# 201_USB3Hub.net
KiCad netlist of a schematic drawn in Altium Designer
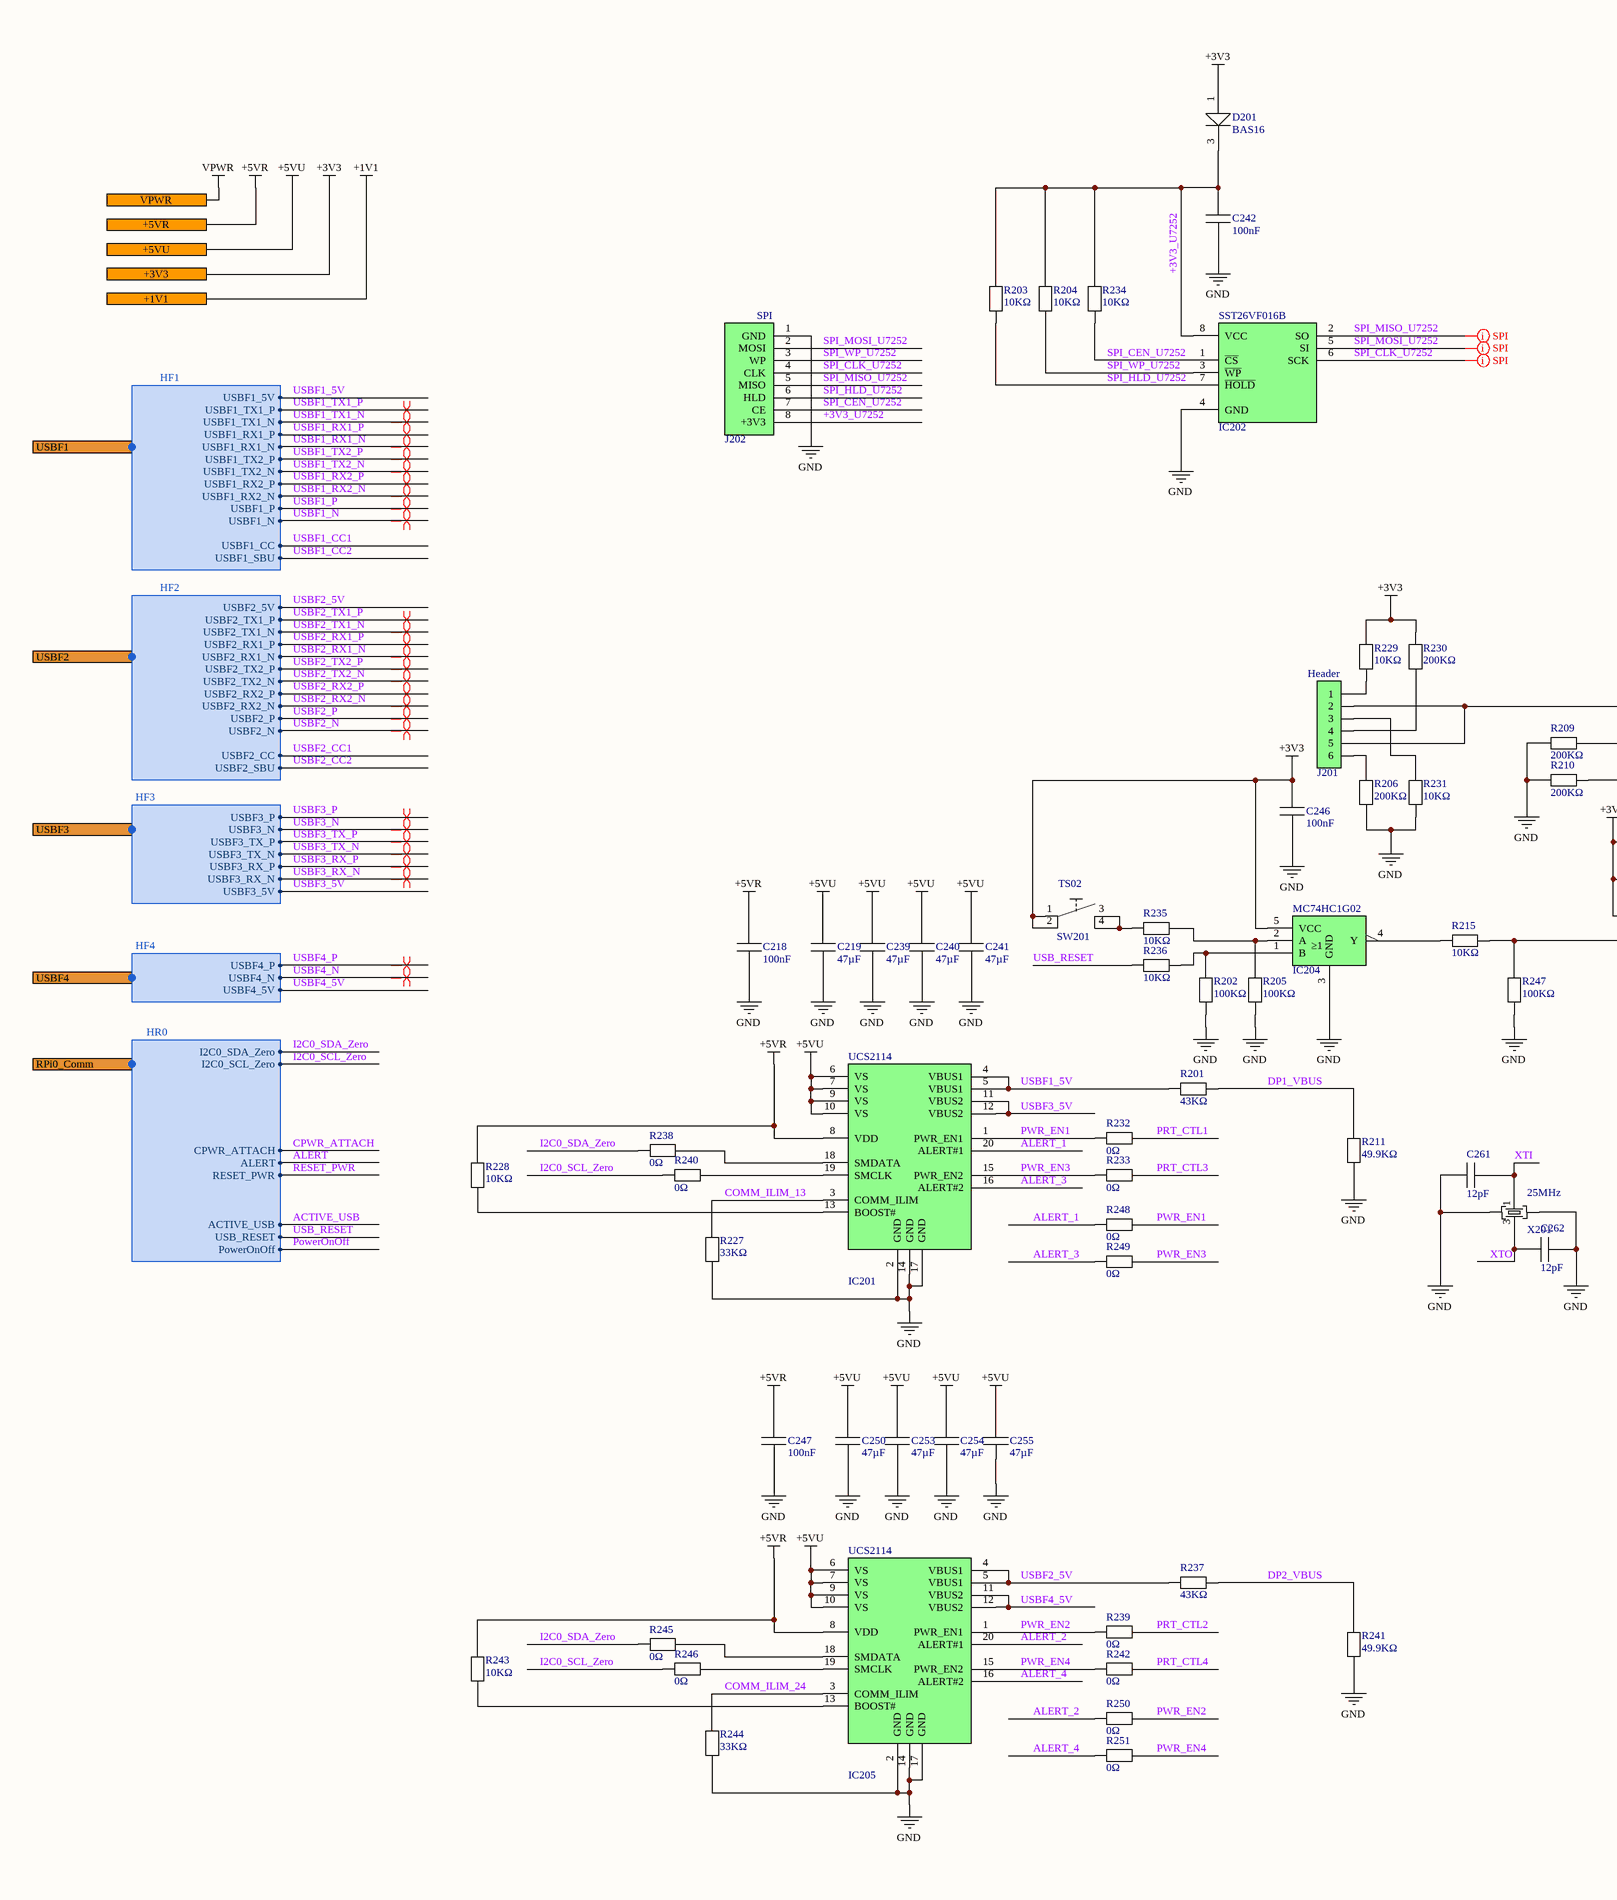
[diagram p0: 201_USB3Hub.SchDoc, left]
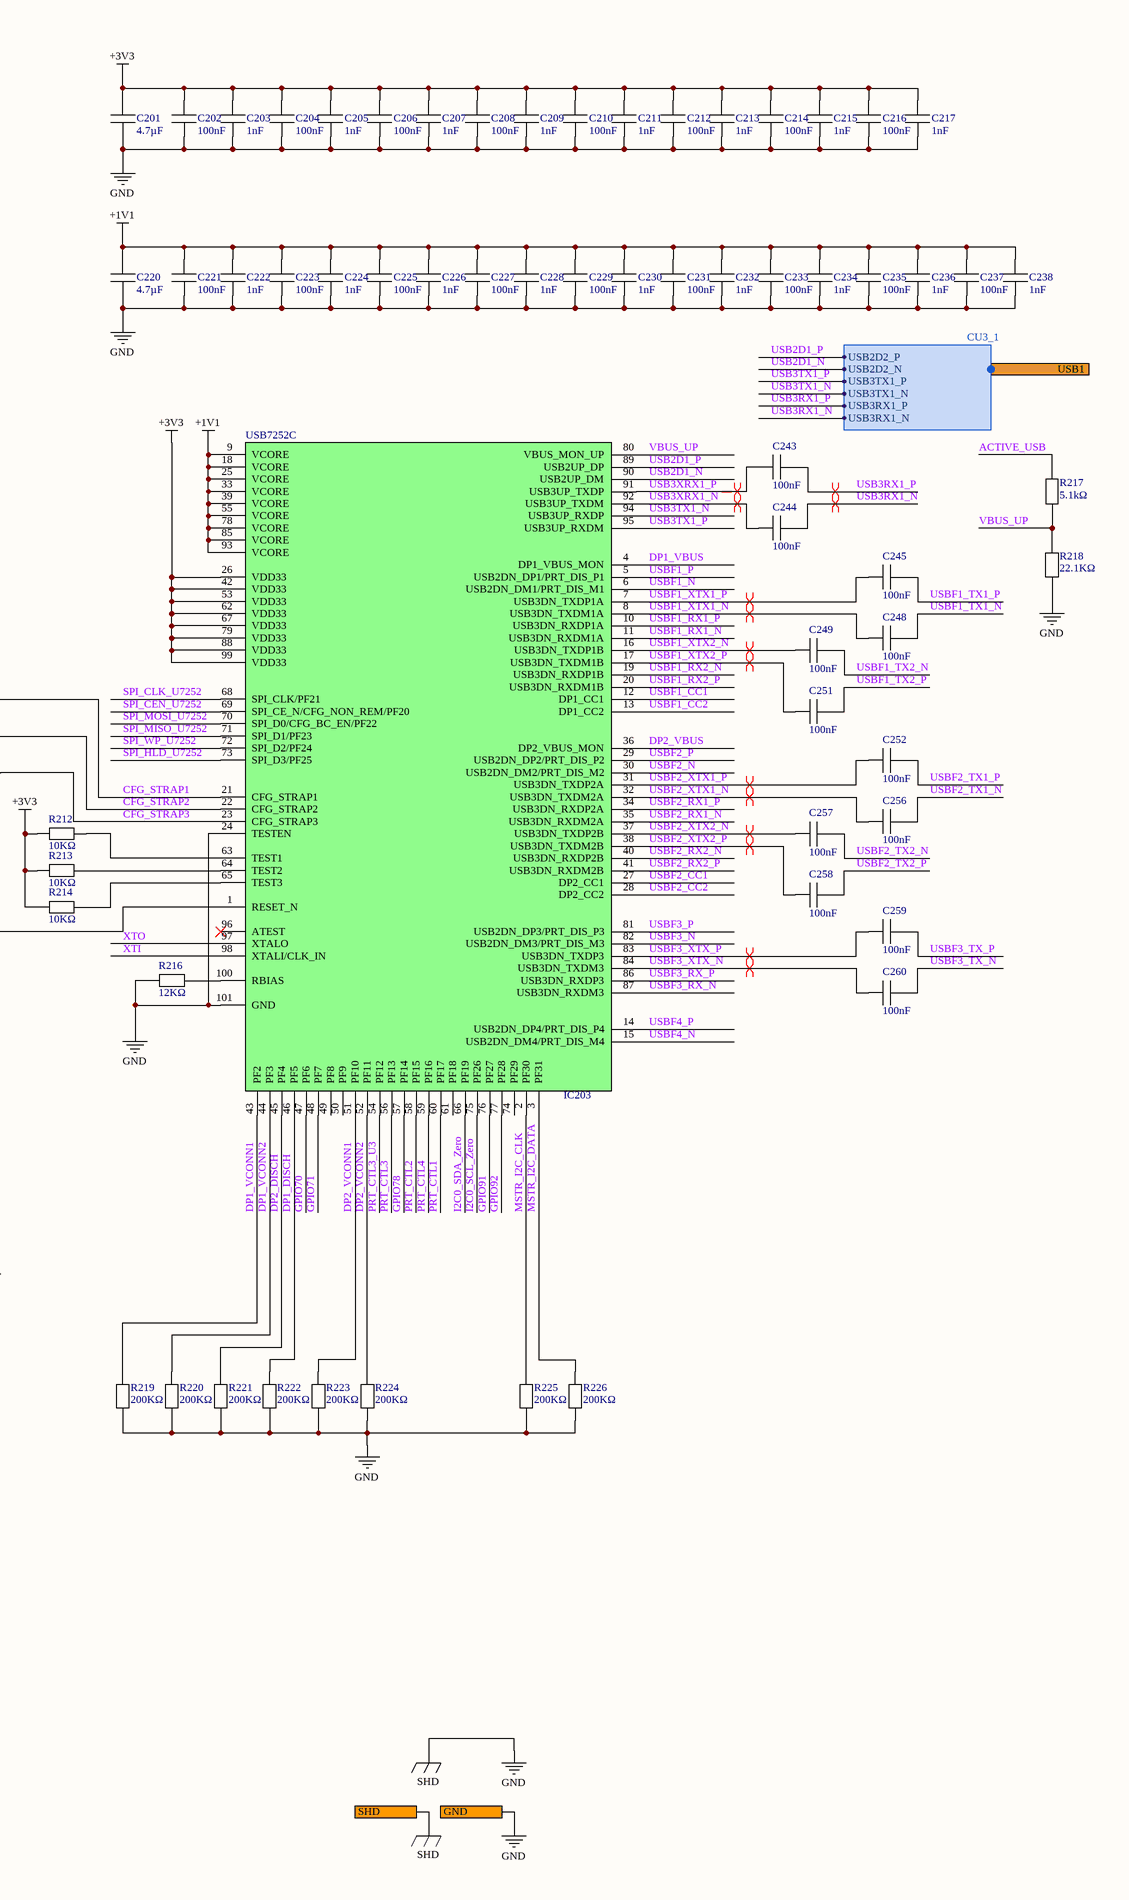
[diagram p1: 201_USB3Hub.SchDoc, right]

(export (version "E")
  (design (tool "Eeschema 10.0.6"))
  (components
    (comp (ref "C201")
      (value "4.7µF")
      (footprint "C0603")
      (description "4.7µF 16V 10% X5R")
      (fields
        (field (name "REFVAL") "4.7µF")
        (field (name "PART NUMBER") "CA0002")
        (field (name "MANFACTPART") "C1608X5R1C475K080AC")
      )
      (libsource (lib "GTS_Database") (part "C"))
    )
    (comp (ref "C202")
      (value "100nF")
      (footprint "C0402")
      (description "100nF 16V 10% X7R")
      (fields
        (field (name "REFVAL") "100nF")
        (field (name "PART NUMBER") "CA0010")
        (field (name "MANFACTPART") "GCM155R71C104KA55D")
      )
      (libsource (lib "GTS_Database") (part "C"))
    )
    (comp (ref "C203")
      (value "1nF")
      (footprint "C0402")
      (description "1nF 50V 1% C0G")
      (fields
        (field (name "REFVAL") "1nF")
        (field (name "PART NUMBER") "CA0031")
        (field (name "MANFACTPART") "GRT1555C1H102FA02D")
      )
      (libsource (lib "GTS_Database") (part "C"))
    )
    (comp (ref "C204")
      (value "100nF")
      (footprint "C0402")
      (description "100nF 16V 10% X7R")
      (fields
        (field (name "REFVAL") "100nF")
        (field (name "PART NUMBER") "CA0010")
        (field (name "MANFACTPART") "GCM155R71C104KA55D")
      )
      (libsource (lib "GTS_Database") (part "C"))
    )
    (comp (ref "C205")
      (value "1nF")
      (footprint "C0402")
      (description "1nF 50V 1% C0G")
      (fields
        (field (name "REFVAL") "1nF")
        (field (name "PART NUMBER") "CA0031")
        (field (name "MANFACTPART") "GRT1555C1H102FA02D")
      )
      (libsource (lib "GTS_Database") (part "C"))
    )
    (comp (ref "C206")
      (value "100nF")
      (footprint "C0402")
      (description "100nF 16V 10% X7R")
      (fields
        (field (name "REFVAL") "100nF")
        (field (name "PART NUMBER") "CA0010")
        (field (name "MANFACTPART") "GCM155R71C104KA55D")
      )
      (libsource (lib "GTS_Database") (part "C"))
    )
    (comp (ref "C207")
      (value "1nF")
      (footprint "C0402")
      (description "1nF 50V 1% C0G")
      (fields
        (field (name "REFVAL") "1nF")
        (field (name "PART NUMBER") "CA0031")
        (field (name "MANFACTPART") "GRT1555C1H102FA02D")
      )
      (libsource (lib "GTS_Database") (part "C"))
    )
    (comp (ref "C208")
      (value "100nF")
      (footprint "C0402")
      (description "100nF 16V 10% X7R")
      (fields
        (field (name "REFVAL") "100nF")
        (field (name "PART NUMBER") "CA0010")
        (field (name "MANFACTPART") "GCM155R71C104KA55D")
      )
      (libsource (lib "GTS_Database") (part "C"))
    )
    (comp (ref "C209")
      (value "1nF")
      (footprint "C0402")
      (description "1nF 50V 1% C0G")
      (fields
        (field (name "REFVAL") "1nF")
        (field (name "PART NUMBER") "CA0031")
        (field (name "MANFACTPART") "GRT1555C1H102FA02D")
      )
      (libsource (lib "GTS_Database") (part "C"))
    )
    (comp (ref "C210")
      (value "100nF")
      (footprint "C0402")
      (description "100nF 16V 10% X7R")
      (fields
        (field (name "REFVAL") "100nF")
        (field (name "PART NUMBER") "CA0010")
        (field (name "MANFACTPART") "GCM155R71C104KA55D")
      )
      (libsource (lib "GTS_Database") (part "C"))
    )
    (comp (ref "C211")
      (value "1nF")
      (footprint "C0402")
      (description "1nF 50V 1% C0G")
      (fields
        (field (name "REFVAL") "1nF")
        (field (name "PART NUMBER") "CA0031")
        (field (name "MANFACTPART") "GRT1555C1H102FA02D")
      )
      (libsource (lib "GTS_Database") (part "C"))
    )
    (comp (ref "C212")
      (value "100nF")
      (footprint "C0402")
      (description "100nF 16V 10% X7R")
      (fields
        (field (name "REFVAL") "100nF")
        (field (name "PART NUMBER") "CA0010")
        (field (name "MANFACTPART") "GCM155R71C104KA55D")
      )
      (libsource (lib "GTS_Database") (part "C"))
    )
    (comp (ref "C213")
      (value "1nF")
      (footprint "C0402")
      (description "1nF 50V 1% C0G")
      (fields
        (field (name "REFVAL") "1nF")
        (field (name "PART NUMBER") "CA0031")
        (field (name "MANFACTPART") "GRT1555C1H102FA02D")
      )
      (libsource (lib "GTS_Database") (part "C"))
    )
    (comp (ref "C214")
      (value "100nF")
      (footprint "C0402")
      (description "100nF 16V 10% X7R")
      (fields
        (field (name "REFVAL") "100nF")
        (field (name "PART NUMBER") "CA0010")
        (field (name "MANFACTPART") "GCM155R71C104KA55D")
      )
      (libsource (lib "GTS_Database") (part "C"))
    )
    (comp (ref "C215")
      (value "1nF")
      (footprint "C0402")
      (description "1nF 50V 1% C0G")
      (fields
        (field (name "REFVAL") "1nF")
        (field (name "PART NUMBER") "CA0031")
        (field (name "MANFACTPART") "GRT1555C1H102FA02D")
      )
      (libsource (lib "GTS_Database") (part "C"))
    )
    (comp (ref "C216")
      (value "100nF")
      (footprint "C0402")
      (description "100nF 16V 10% X7R")
      (fields
        (field (name "REFVAL") "100nF")
        (field (name "PART NUMBER") "CA0010")
        (field (name "MANFACTPART") "GCM155R71C104KA55D")
      )
      (libsource (lib "GTS_Database") (part "C"))
    )
    (comp (ref "C217")
      (value "1nF")
      (footprint "C0402")
      (description "1nF 50V 1% C0G")
      (fields
        (field (name "REFVAL") "1nF")
        (field (name "PART NUMBER") "CA0031")
        (field (name "MANFACTPART") "GRT1555C1H102FA02D")
      )
      (libsource (lib "GTS_Database") (part "C"))
    )
    (comp (ref "C218")
      (value "100nF")
      (footprint "C0402")
      (description "100nF 16V 10% X7R")
      (fields
        (field (name "REFVAL") "100nF")
        (field (name "PART NUMBER") "CA0010")
        (field (name "MANFACTPART") "GCM155R71C104KA55D")
      )
      (libsource (lib "GTS_Database") (part "C"))
    )
    (comp (ref "C219")
      (value "47µF")
      (footprint "C1210")
      (description "47µF 16V 20% X5R")
      (fields
        (field (name "REFVAL") "47µF")
        (field (name "PART NUMBER") "CA0007")
        (field (name "MANFACTPART") "EMK325ABJ476MM8P")
      )
      (libsource (lib "GTS_Database") (part "C"))
    )
    (comp (ref "C220")
      (value "4.7µF")
      (footprint "C0603")
      (description "4.7µF 16V 10% X5R")
      (fields
        (field (name "REFVAL") "4.7µF")
        (field (name "PART NUMBER") "CA0002")
        (field (name "MANFACTPART") "C1608X5R1C475K080AC")
      )
      (libsource (lib "GTS_Database") (part "C"))
    )
    (comp (ref "C221")
      (value "100nF")
      (footprint "C0402")
      (description "100nF 16V 10% X7R")
      (fields
        (field (name "REFVAL") "100nF")
        (field (name "PART NUMBER") "CA0010")
        (field (name "MANFACTPART") "GCM155R71C104KA55D")
      )
      (libsource (lib "GTS_Database") (part "C"))
    )
    (comp (ref "C222")
      (value "1nF")
      (footprint "C0402")
      (description "1nF 50V 1% C0G")
      (fields
        (field (name "REFVAL") "1nF")
        (field (name "PART NUMBER") "CA0031")
        (field (name "MANFACTPART") "GRT1555C1H102FA02D")
      )
      (libsource (lib "GTS_Database") (part "C"))
    )
    (comp (ref "C223")
      (value "100nF")
      (footprint "C0402")
      (description "100nF 16V 10% X7R")
      (fields
        (field (name "REFVAL") "100nF")
        (field (name "PART NUMBER") "CA0010")
        (field (name "MANFACTPART") "GCM155R71C104KA55D")
      )
      (libsource (lib "GTS_Database") (part "C"))
    )
    (comp (ref "C224")
      (value "1nF")
      (footprint "C0402")
      (description "1nF 50V 1% C0G")
      (fields
        (field (name "REFVAL") "1nF")
        (field (name "PART NUMBER") "CA0031")
        (field (name "MANFACTPART") "GRT1555C1H102FA02D")
      )
      (libsource (lib "GTS_Database") (part "C"))
    )
    (comp (ref "C225")
      (value "100nF")
      (footprint "C0402")
      (description "100nF 16V 10% X7R")
      (fields
        (field (name "REFVAL") "100nF")
        (field (name "PART NUMBER") "CA0010")
        (field (name "MANFACTPART") "GCM155R71C104KA55D")
      )
      (libsource (lib "GTS_Database") (part "C"))
    )
    (comp (ref "C226")
      (value "1nF")
      (footprint "C0402")
      (description "1nF 50V 1% C0G")
      (fields
        (field (name "REFVAL") "1nF")
        (field (name "PART NUMBER") "CA0031")
        (field (name "MANFACTPART") "GRT1555C1H102FA02D")
      )
      (libsource (lib "GTS_Database") (part "C"))
    )
    (comp (ref "C227")
      (value "100nF")
      (footprint "C0402")
      (description "100nF 16V 10% X7R")
      (fields
        (field (name "REFVAL") "100nF")
        (field (name "PART NUMBER") "CA0010")
        (field (name "MANFACTPART") "GCM155R71C104KA55D")
      )
      (libsource (lib "GTS_Database") (part "C"))
    )
    (comp (ref "C228")
      (value "1nF")
      (footprint "C0402")
      (description "1nF 50V 1% C0G")
      (fields
        (field (name "REFVAL") "1nF")
        (field (name "PART NUMBER") "CA0031")
        (field (name "MANFACTPART") "GRT1555C1H102FA02D")
      )
      (libsource (lib "GTS_Database") (part "C"))
    )
    (comp (ref "C229")
      (value "100nF")
      (footprint "C0402")
      (description "100nF 16V 10% X7R")
      (fields
        (field (name "REFVAL") "100nF")
        (field (name "PART NUMBER") "CA0010")
        (field (name "MANFACTPART") "GCM155R71C104KA55D")
      )
      (libsource (lib "GTS_Database") (part "C"))
    )
    (comp (ref "C230")
      (value "1nF")
      (footprint "C0402")
      (description "1nF 50V 1% C0G")
      (fields
        (field (name "REFVAL") "1nF")
        (field (name "PART NUMBER") "CA0031")
        (field (name "MANFACTPART") "GRT1555C1H102FA02D")
      )
      (libsource (lib "GTS_Database") (part "C"))
    )
    (comp (ref "C231")
      (value "100nF")
      (footprint "C0402")
      (description "100nF 16V 10% X7R")
      (fields
        (field (name "REFVAL") "100nF")
        (field (name "PART NUMBER") "CA0010")
        (field (name "MANFACTPART") "GCM155R71C104KA55D")
      )
      (libsource (lib "GTS_Database") (part "C"))
    )
    (comp (ref "C232")
      (value "1nF")
      (footprint "C0402")
      (description "1nF 50V 1% C0G")
      (fields
        (field (name "REFVAL") "1nF")
        (field (name "PART NUMBER") "CA0031")
        (field (name "MANFACTPART") "GRT1555C1H102FA02D")
      )
      (libsource (lib "GTS_Database") (part "C"))
    )
    (comp (ref "C233")
      (value "100nF")
      (footprint "C0402")
      (description "100nF 16V 10% X7R")
      (fields
        (field (name "REFVAL") "100nF")
        (field (name "PART NUMBER") "CA0010")
        (field (name "MANFACTPART") "GCM155R71C104KA55D")
      )
      (libsource (lib "GTS_Database") (part "C"))
    )
    (comp (ref "C234")
      (value "1nF")
      (footprint "C0402")
      (description "1nF 50V 1% C0G")
      (fields
        (field (name "REFVAL") "1nF")
        (field (name "PART NUMBER") "CA0031")
        (field (name "MANFACTPART") "GRT1555C1H102FA02D")
      )
      (libsource (lib "GTS_Database") (part "C"))
    )
    (comp (ref "C235")
      (value "100nF")
      (footprint "C0402")
      (description "100nF 16V 10% X7R")
      (fields
        (field (name "REFVAL") "100nF")
        (field (name "PART NUMBER") "CA0010")
        (field (name "MANFACTPART") "GCM155R71C104KA55D")
      )
      (libsource (lib "GTS_Database") (part "C"))
    )
    (comp (ref "C236")
      (value "1nF")
      (footprint "C0402")
      (description "1nF 50V 1% C0G")
      (fields
        (field (name "REFVAL") "1nF")
        (field (name "PART NUMBER") "CA0031")
        (field (name "MANFACTPART") "GRT1555C1H102FA02D")
      )
      (libsource (lib "GTS_Database") (part "C"))
    )
    (comp (ref "C237")
      (value "100nF")
      (footprint "C0402")
      (description "100nF 16V 10% X7R")
      (fields
        (field (name "REFVAL") "100nF")
        (field (name "PART NUMBER") "CA0010")
        (field (name "MANFACTPART") "GCM155R71C104KA55D")
      )
      (libsource (lib "GTS_Database") (part "C"))
    )
    (comp (ref "C238")
      (value "1nF")
      (footprint "C0402")
      (description "1nF 50V 1% C0G")
      (fields
        (field (name "REFVAL") "1nF")
        (field (name "PART NUMBER") "CA0031")
        (field (name "MANFACTPART") "GRT1555C1H102FA02D")
      )
      (libsource (lib "GTS_Database") (part "C"))
    )
    (comp (ref "C239")
      (value "47µF")
      (footprint "C1210")
      (description "47µF 16V 20% X5R")
      (fields
        (field (name "REFVAL") "47µF")
        (field (name "PART NUMBER") "CA0007")
        (field (name "MANFACTPART") "EMK325ABJ476MM8P")
      )
      (libsource (lib "GTS_Database") (part "C"))
    )
    (comp (ref "C240")
      (value "47µF")
      (footprint "C1210")
      (description "47µF 16V 20% X5R")
      (fields
        (field (name "REFVAL") "47µF")
        (field (name "PART NUMBER") "CA0007")
        (field (name "MANFACTPART") "EMK325ABJ476MM8P")
      )
      (libsource (lib "GTS_Database") (part "C"))
    )
    (comp (ref "C241")
      (value "47µF")
      (footprint "C1210")
      (description "47µF 16V 20% X5R")
      (fields
        (field (name "REFVAL") "47µF")
        (field (name "PART NUMBER") "CA0007")
        (field (name "MANFACTPART") "EMK325ABJ476MM8P")
      )
      (libsource (lib "GTS_Database") (part "C"))
    )
    (comp (ref "C242")
      (value "100nF")
      (footprint "C0402")
      (description "100nF 16V 10% X7R")
      (fields
        (field (name "REFVAL") "100nF")
        (field (name "PART NUMBER") "CA0010")
        (field (name "MANFACTPART") "GCM155R71C104KA55D")
      )
      (libsource (lib "GTS_Database") (part "C"))
    )
    (comp (ref "C243")
      (value "100nF")
      (footprint "C0402")
      (description "100nF 16V 10% X7R")
      (fields
        (field (name "REFVAL") "100nF")
        (field (name "PART NUMBER") "CA0010")
        (field (name "MANFACTPART") "GCM155R71C104KA55D")
      )
      (libsource (lib "GTS_Database") (part "C"))
    )
    (comp (ref "C244")
      (value "100nF")
      (footprint "C0402")
      (description "100nF 16V 10% X7R")
      (fields
        (field (name "REFVAL") "100nF")
        (field (name "PART NUMBER") "CA0010")
        (field (name "MANFACTPART") "GCM155R71C104KA55D")
      )
      (libsource (lib "GTS_Database") (part "C"))
    )
    (comp (ref "C245")
      (value "100nF")
      (footprint "C0402")
      (description "100nF 16V 10% X7R")
      (fields
        (field (name "REFVAL") "100nF")
        (field (name "PART NUMBER") "CA0010")
        (field (name "MANFACTPART") "GCM155R71C104KA55D")
      )
      (libsource (lib "GTS_Database") (part "C"))
    )
    (comp (ref "C246")
      (value "100nF")
      (footprint "C0402")
      (description "100nF 16V 10% X7R")
      (fields
        (field (name "REFVAL") "100nF")
        (field (name "PART NUMBER") "CA0010")
        (field (name "MANFACTPART") "GCM155R71C104KA55D")
      )
      (libsource (lib "GTS_Database") (part "C"))
    )
    (comp (ref "C247")
      (value "100nF")
      (footprint "C0402")
      (description "100nF 16V 10% X7R")
      (fields
        (field (name "REFVAL") "100nF")
        (field (name "PART NUMBER") "CA0010")
        (field (name "MANFACTPART") "GCM155R71C104KA55D")
      )
      (libsource (lib "GTS_Database") (part "C"))
    )
    (comp (ref "C248")
      (value "100nF")
      (footprint "C0402")
      (description "100nF 16V 10% X7R")
      (fields
        (field (name "REFVAL") "100nF")
        (field (name "PART NUMBER") "CA0010")
        (field (name "MANFACTPART") "GCM155R71C104KA55D")
      )
      (libsource (lib "GTS_Database") (part "C"))
    )
    (comp (ref "C249")
      (value "100nF")
      (footprint "C0402")
      (description "100nF 16V 10% X7R")
      (fields
        (field (name "REFVAL") "100nF")
        (field (name "PART NUMBER") "CA0010")
        (field (name "MANFACTPART") "GCM155R71C104KA55D")
      )
      (libsource (lib "GTS_Database") (part "C"))
    )
    (comp (ref "C250")
      (value "47µF")
      (footprint "C1210")
      (description "47µF 16V 20% X5R")
      (fields
        (field (name "REFVAL") "47µF")
        (field (name "PART NUMBER") "CA0007")
        (field (name "MANFACTPART") "EMK325ABJ476MM8P")
      )
      (libsource (lib "GTS_Database") (part "C"))
    )
    (comp (ref "C251")
      (value "100nF")
      (footprint "C0402")
      (description "100nF 16V 10% X7R")
      (fields
        (field (name "REFVAL") "100nF")
        (field (name "PART NUMBER") "CA0010")
        (field (name "MANFACTPART") "GCM155R71C104KA55D")
      )
      (libsource (lib "GTS_Database") (part "C"))
    )
    (comp (ref "C252")
      (value "100nF")
      (footprint "C0402")
      (description "100nF 16V 10% X7R")
      (fields
        (field (name "REFVAL") "100nF")
        (field (name "PART NUMBER") "CA0010")
        (field (name "MANFACTPART") "GCM155R71C104KA55D")
      )
      (libsource (lib "GTS_Database") (part "C"))
    )
    (comp (ref "C253")
      (value "47µF")
      (footprint "C1210")
      (description "47µF 16V 20% X5R")
      (fields
        (field (name "REFVAL") "47µF")
        (field (name "PART NUMBER") "CA0007")
        (field (name "MANFACTPART") "EMK325ABJ476MM8P")
      )
      (libsource (lib "GTS_Database") (part "C"))
    )
    (comp (ref "C254")
      (value "47µF")
      (footprint "C1210")
      (description "47µF 16V 20% X5R")
      (fields
        (field (name "REFVAL") "47µF")
        (field (name "PART NUMBER") "CA0007")
        (field (name "MANFACTPART") "EMK325ABJ476MM8P")
      )
      (libsource (lib "GTS_Database") (part "C"))
    )
    (comp (ref "C255")
      (value "47µF")
      (footprint "C1210")
      (description "47µF 16V 20% X5R")
      (fields
        (field (name "REFVAL") "47µF")
        (field (name "PART NUMBER") "CA0007")
        (field (name "MANFACTPART") "EMK325ABJ476MM8P")
      )
      (libsource (lib "GTS_Database") (part "C"))
    )
    (comp (ref "C256")
      (value "100nF")
      (footprint "C0402")
      (description "100nF 16V 10% X7R")
      (fields
        (field (name "REFVAL") "100nF")
        (field (name "PART NUMBER") "CA0010")
        (field (name "MANFACTPART") "GCM155R71C104KA55D")
      )
      (libsource (lib "GTS_Database") (part "C"))
    )
    (comp (ref "C257")
      (value "100nF")
      (footprint "C0402")
      (description "100nF 16V 10% X7R")
      (fields
        (field (name "REFVAL") "100nF")
        (field (name "PART NUMBER") "CA0010")
        (field (name "MANFACTPART") "GCM155R71C104KA55D")
      )
      (libsource (lib "GTS_Database") (part "C"))
    )
    (comp (ref "C258")
      (value "100nF")
      (footprint "C0402")
      (description "100nF 16V 10% X7R")
      (fields
        (field (name "REFVAL") "100nF")
        (field (name "PART NUMBER") "CA0010")
        (field (name "MANFACTPART") "GCM155R71C104KA55D")
      )
      (libsource (lib "GTS_Database") (part "C"))
    )
    (comp (ref "C259")
      (value "100nF")
      (footprint "C0402")
      (description "100nF 16V 10% X7R")
      (fields
        (field (name "REFVAL") "100nF")
        (field (name "PART NUMBER") "CA0010")
        (field (name "MANFACTPART") "GCM155R71C104KA55D")
      )
      (libsource (lib "GTS_Database") (part "C"))
    )
    (comp (ref "C260")
      (value "100nF")
      (footprint "C0402")
      (description "100nF 16V 10% X7R")
      (fields
        (field (name "REFVAL") "100nF")
        (field (name "PART NUMBER") "CA0010")
        (field (name "MANFACTPART") "GCM155R71C104KA55D")
      )
      (libsource (lib "GTS_Database") (part "C"))
    )
    (comp (ref "C261")
      (value "12pF")
      (footprint "C0402")
      (description "12pF 16V 1% C0G")
      (fields
        (field (name "REFVAL") "12pF")
        (field (name "PART NUMBER") "CA0059")
        (field (name "MANFACTPART") "VJ0402A120FXJCW1BC")
      )
      (libsource (lib "GTS_Database") (part "C"))
    )
    (comp (ref "C262")
      (value "12pF")
      (footprint "C0402")
      (description "12pF 16V 1% C0G")
      (fields
        (field (name "REFVAL") "12pF")
        (field (name "PART NUMBER") "CA0059")
        (field (name "MANFACTPART") "VJ0402A120FXJCW1BC")
      )
      (libsource (lib "GTS_Database") (part "C"))
    )
    (comp (ref "D201")
      (value "BAS16")
      (footprint "SOT-23")
      (description "Diodes - General Purpose, Power, Switching 100Vll Signal Switching Diodes 2A")
      (fields
        (field (name "REFVAL") "BAS16")
        (field (name "PART NUMBER") "DI0010")
        (field (name "MANFACTPART") "BAS16_R1_00001")
      )
      (libsource (lib "GTS_Database") (part "Ddefault_3P"))
    )
    (comp (ref "IC201")
      (value "UCS2114")
      (footprint "VQFN-20_3X3")
      (description "Dual USB Power Switch with Integrated Current Sensor")
      (fields (field (name "REFVAL") "UCS2114") (field (name "PART NUMBER") "IC0056"))
      (libsource (lib "GTS_Database") (part "UCS2114"))
    )
    (comp (ref "IC202")
      (value "SST26VF016B")
      (footprint "SO-8")
      (description "16 Mbit Serial Quad I/O (SQI) Flash Memory")
      (fields
        (field (name "REFVAL") "SST26VF016B")
        (field (name "PART NUMBER") "IC0059")
        (field (name "MANFACTPART") "SST26VF016B-104V/SN")
      )
      (libsource (lib "GTS_Database") (part "SST26VF016B"))
    )
    (comp (ref "IC203")
      (value "USB7252C")
      (footprint "VQFN-100G_12X12")
      (description "4-Port USB 3.2 Gen 2 Type-C Controller Hub")
      (fields (field (name "REFVAL") "USB7252C") (field (name "PART NUMBER") "IC0047"))
      (libsource (lib "GTS_Database") (part "USB7252C"))
    )
    (comp (ref "IC204")
      (value "MC74HC1G02")
      (footprint "TSOP-5")
      (description "Logic Gates 2-6V Single 2-Input NOR")
      (fields
        (field (name "REFVAL") "MC74HC1G02")
        (field (name "PART NUMBER") "IC0061")
        (field (name "MANFACTPART") "MC74HC1G02DTT1G")
      )
      (libsource (lib "GTS_Database") (part "MC74HC1G02"))
    )
    (comp (ref "IC205")
      (value "UCS2114")
      (footprint "VQFN-20_3X3")
      (description "Dual USB Power Switch with Integrated Current Sensor")
      (fields (field (name "REFVAL") "UCS2114") (field (name "PART NUMBER") "IC0056"))
      (libsource (lib "GTS_Database") (part "UCS2114"))
    )
    (comp (ref "J201")
      (value "Header")
      (footprint "1X6P_2.54MM_SMT")
      (description "Header 1x6P SMT Mount")
      (fields
        (field (name "REFVAL") "Header")
        (field (name "PART NUMBER") "CO0043")
        (field (name "MANFACTPART") "G800MJ302018EU")
      )
      (libsource (lib "GTS_Database") (part "CONN1X6P"))
    )
    (comp (ref "J202")
      (value "SPI")
      (footprint "SPI_PROG_TYPE1")
      (description "SPI Programming connection")
      (fields (field (name "REFVAL") "SPI") (field (name "PART NUMBER") "ME0028"))
      (libsource (lib "GTS_Database") (part "SPI_PROG_TYPE1"))
    )
    (comp (ref "R201")
      (value "43KΩ")
      (footprint "R0402")
      (description "43KΩ 1% 62.5mW 100PPM")
      (fields
        (field (name "REFVAL") "43KΩ")
        (field (name "PART NUMBER") "RS0076")
        (field (name "MANFACTPART") "CRCW040243K0FKEDC")
      )
      (libsource (lib "GTS_Database") (part "R"))
    )
    (comp (ref "R202")
      (value "100KΩ")
      (footprint "R0402")
      (description "100KΩ 1% 62.5mW 100PPM")
      (fields
        (field (name "REFVAL") "100KΩ")
        (field (name "PART NUMBER") "RS0036")
        (field (name "MANFACTPART") "AC0402FR-13100KL")
      )
      (libsource (lib "GTS_Database") (part "R"))
    )
    (comp (ref "R203")
      (value "10KΩ")
      (footprint "R0402")
      (description "10KΩ 1% 62.5mW")
      (fields
        (field (name "REFVAL") "10KΩ")
        (field (name "PART NUMBER") "RS0011")
        (field (name "MANFACTPART") "WR04X1002FTL")
      )
      (libsource (lib "GTS_Database") (part "R"))
    )
    (comp (ref "R204")
      (value "10KΩ")
      (footprint "R0402")
      (description "10KΩ 1% 62.5mW")
      (fields
        (field (name "REFVAL") "10KΩ")
        (field (name "PART NUMBER") "RS0011")
        (field (name "MANFACTPART") "WR04X1002FTL")
      )
      (libsource (lib "GTS_Database") (part "R"))
    )
    (comp (ref "R205")
      (value "100KΩ")
      (footprint "R0402")
      (description "100KΩ 1% 62.5mW 100PPM")
      (fields
        (field (name "REFVAL") "100KΩ")
        (field (name "PART NUMBER") "RS0036")
        (field (name "MANFACTPART") "AC0402FR-13100KL")
      )
      (libsource (lib "GTS_Database") (part "R"))
    )
    (comp (ref "R206")
      (value "200KΩ")
      (footprint "R0402")
      (description "200KΩ 1% 62.5mW 100PPM")
      (fields
        (field (name "REFVAL") "200KΩ")
        (field (name "PART NUMBER") "RS0045")
        (field (name "MANFACTPART") "CRG0402F200K")
      )
      (libsource (lib "GTS_Database") (part "R"))
    )
    (comp (ref "R209")
      (value "200KΩ")
      (footprint "R0402")
      (description "200KΩ 1% 62.5mW 100PPM")
      (fields
        (field (name "REFVAL") "200KΩ")
        (field (name "PART NUMBER") "RS0045")
        (field (name "MANFACTPART") "CRG0402F200K")
      )
      (libsource (lib "GTS_Database") (part "R"))
    )
    (comp (ref "R210")
      (value "200KΩ")
      (footprint "R0402")
      (description "200KΩ 1% 62.5mW 100PPM")
      (fields
        (field (name "REFVAL") "200KΩ")
        (field (name "PART NUMBER") "RS0045")
        (field (name "MANFACTPART") "CRG0402F200K")
      )
      (libsource (lib "GTS_Database") (part "R"))
    )
    (comp (ref "R211")
      (value "49.9KΩ")
      (footprint "R0402")
      (description "49.9KΩ 1% 62.5mW 100PPM")
      (fields
        (field (name "REFVAL") "49.9KΩ")
        (field (name "PART NUMBER") "RS0077")
        (field (name "MANFACTPART") "0402WGF4992TCE")
      )
      (libsource (lib "GTS_Database") (part "R"))
    )
    (comp (ref "R212")
      (value "10KΩ")
      (footprint "R0402")
      (description "10KΩ 1% 62.5mW")
      (fields
        (field (name "REFVAL") "10KΩ")
        (field (name "PART NUMBER") "RS0011")
        (field (name "MANFACTPART") "WR04X1002FTL")
      )
      (libsource (lib "GTS_Database") (part "R"))
    )
    (comp (ref "R213")
      (value "10KΩ")
      (footprint "R0402")
      (description "10KΩ 1% 62.5mW")
      (fields
        (field (name "REFVAL") "10KΩ")
        (field (name "PART NUMBER") "RS0011")
        (field (name "MANFACTPART") "WR04X1002FTL")
      )
      (libsource (lib "GTS_Database") (part "R"))
    )
    (comp (ref "R214")
      (value "10KΩ")
      (footprint "R0402")
      (description "10KΩ 1% 62.5mW")
      (fields
        (field (name "REFVAL") "10KΩ")
        (field (name "PART NUMBER") "RS0011")
        (field (name "MANFACTPART") "WR04X1002FTL")
      )
      (libsource (lib "GTS_Database") (part "R"))
    )
    (comp (ref "R215")
      (value "10KΩ")
      (footprint "R0402")
      (description "10KΩ 1% 62.5mW")
      (fields
        (field (name "REFVAL") "10KΩ")
        (field (name "PART NUMBER") "RS0011")
        (field (name "MANFACTPART") "WR04X1002FTL")
      )
      (libsource (lib "GTS_Database") (part "R"))
    )
    (comp (ref "R216")
      (value "12KΩ")
      (footprint "R0402")
      (description "12KΩ 1% 62.5mW")
      (fields
        (field (name "REFVAL") "12KΩ")
        (field (name "PART NUMBER") "RS0015")
        (field (name "MANFACTPART") "RC0402FR-1312KL")
      )
      (libsource (lib "GTS_Database") (part "R"))
    )
    (comp (ref "R217")
      (value "5.1kΩ")
      (footprint "R0402")
      (description "5.1KΩ 1% 62.5mW 100PPM")
      (fields
        (field (name "REFVAL") "5.1kΩ")
        (field (name "PART NUMBER") "RS0038")
        (field (name "MANFACTPART") "CRCW04025K10FKEDC")
      )
      (libsource (lib "GTS_Database") (part "R"))
    )
    (comp (ref "R218")
      (value "22.1KΩ")
      (footprint "R0603")
      (description "22.1KΩ 1% 100mW 100PPM")
      (fields
        (field (name "REFVAL") "22.1KΩ")
        (field (name "PART NUMBER") "RS0040")
        (field (name "MANFACTPART") "RC0603FR-0722K1L")
      )
      (libsource (lib "GTS_Database") (part "R"))
    )
    (comp (ref "R219")
      (value "200KΩ")
      (footprint "R0402")
      (description "200KΩ 1% 62.5mW 100PPM")
      (fields
        (field (name "REFVAL") "200KΩ")
        (field (name "PART NUMBER") "RS0045")
        (field (name "MANFACTPART") "CRG0402F200K")
      )
      (libsource (lib "GTS_Database") (part "R"))
    )
    (comp (ref "R220")
      (value "200KΩ")
      (footprint "R0402")
      (description "200KΩ 1% 62.5mW 100PPM")
      (fields
        (field (name "REFVAL") "200KΩ")
        (field (name "PART NUMBER") "RS0045")
        (field (name "MANFACTPART") "CRG0402F200K")
      )
      (libsource (lib "GTS_Database") (part "R"))
    )
    (comp (ref "R221")
      (value "200KΩ")
      (footprint "R0402")
      (description "200KΩ 1% 62.5mW 100PPM")
      (fields
        (field (name "REFVAL") "200KΩ")
        (field (name "PART NUMBER") "RS0045")
        (field (name "MANFACTPART") "CRG0402F200K")
      )
      (libsource (lib "GTS_Database") (part "R"))
    )
    (comp (ref "R222")
      (value "200KΩ")
      (footprint "R0402")
      (description "200KΩ 1% 62.5mW 100PPM")
      (fields
        (field (name "REFVAL") "200KΩ")
        (field (name "PART NUMBER") "RS0045")
        (field (name "MANFACTPART") "CRG0402F200K")
      )
      (libsource (lib "GTS_Database") (part "R"))
    )
    (comp (ref "R223")
      (value "200KΩ")
      (footprint "R0402")
      (description "200KΩ 1% 62.5mW 100PPM")
      (fields
        (field (name "REFVAL") "200KΩ")
        (field (name "PART NUMBER") "RS0045")
        (field (name "MANFACTPART") "CRG0402F200K")
      )
      (libsource (lib "GTS_Database") (part "R"))
    )
    (comp (ref "R224")
      (value "200KΩ")
      (footprint "R0402")
      (description "200KΩ 1% 62.5mW 100PPM")
      (fields
        (field (name "REFVAL") "200KΩ")
        (field (name "PART NUMBER") "RS0045")
        (field (name "MANFACTPART") "CRG0402F200K")
      )
      (libsource (lib "GTS_Database") (part "R"))
    )
    (comp (ref "R225")
      (value "200KΩ")
      (footprint "R0402")
      (description "200KΩ 1% 62.5mW 100PPM")
      (fields
        (field (name "REFVAL") "200KΩ")
        (field (name "PART NUMBER") "RS0045")
        (field (name "MANFACTPART") "CRG0402F200K")
      )
      (libsource (lib "GTS_Database") (part "R"))
    )
    (comp (ref "R226")
      (value "200KΩ")
      (footprint "R0402")
      (description "200KΩ 1% 62.5mW 100PPM")
      (fields
        (field (name "REFVAL") "200KΩ")
        (field (name "PART NUMBER") "RS0045")
        (field (name "MANFACTPART") "CRG0402F200K")
      )
      (libsource (lib "GTS_Database") (part "R"))
    )
    (comp (ref "R227")
      (value "33KΩ")
      (footprint "R0402")
      (description "33KΩ 1% 62.5mW 100PPM")
      (fields
        (field (name "REFVAL") "33KΩ")
        (field (name "PART NUMBER") "RS0075")
        (field (name "MANFACTPART") "0402WGF3302TCE")
      )
      (libsource (lib "GTS_Database") (part "R"))
    )
    (comp (ref "R228")
      (value "10KΩ")
      (footprint "R0402")
      (description "10KΩ 1% 62.5mW")
      (fields
        (field (name "REFVAL") "10KΩ")
        (field (name "PART NUMBER") "RS0011")
        (field (name "MANFACTPART") "WR04X1002FTL")
      )
      (libsource (lib "GTS_Database") (part "R"))
    )
    (comp (ref "R229")
      (value "10KΩ")
      (footprint "R0402")
      (description "10KΩ 1% 62.5mW")
      (fields
        (field (name "REFVAL") "10KΩ")
        (field (name "PART NUMBER") "RS0011")
        (field (name "MANFACTPART") "WR04X1002FTL")
      )
      (libsource (lib "GTS_Database") (part "R"))
    )
    (comp (ref "R230")
      (value "200KΩ")
      (footprint "R0402")
      (description "200KΩ 1% 62.5mW 100PPM")
      (fields
        (field (name "REFVAL") "200KΩ")
        (field (name "PART NUMBER") "RS0045")
        (field (name "MANFACTPART") "CRG0402F200K")
      )
      (libsource (lib "GTS_Database") (part "R"))
    )
    (comp (ref "R231")
      (value "10KΩ")
      (footprint "R0402")
      (description "10KΩ 1% 62.5mW")
      (fields
        (field (name "REFVAL") "10KΩ")
        (field (name "PART NUMBER") "RS0011")
        (field (name "MANFACTPART") "WR04X1002FTL")
      )
      (libsource (lib "GTS_Database") (part "R"))
    )
    (comp (ref "R232")
      (value "0Ω")
      (footprint "R0402")
      (description "0Ω 62.5mW")
      (fields
        (field (name "REFVAL") "0Ω")
        (field (name "PART NUMBER") "RS0074")
        (field (name "MANFACTPART") "0402WGJ0000TCE")
      )
      (libsource (lib "GTS_Database") (part "R"))
    )
    (comp (ref "R233")
      (value "0Ω")
      (footprint "R0402")
      (description "0Ω 62.5mW")
      (fields
        (field (name "REFVAL") "0Ω")
        (field (name "PART NUMBER") "RS0074")
        (field (name "MANFACTPART") "0402WGJ0000TCE")
      )
      (libsource (lib "GTS_Database") (part "R"))
    )
    (comp (ref "R234")
      (value "10KΩ")
      (footprint "R0402")
      (description "10KΩ 1% 62.5mW")
      (fields
        (field (name "REFVAL") "10KΩ")
        (field (name "PART NUMBER") "RS0011")
        (field (name "MANFACTPART") "WR04X1002FTL")
      )
      (libsource (lib "GTS_Database") (part "R"))
    )
    (comp (ref "R235")
      (value "10KΩ")
      (footprint "R0402")
      (description "10KΩ 1% 62.5mW")
      (fields
        (field (name "REFVAL") "10KΩ")
        (field (name "PART NUMBER") "RS0011")
        (field (name "MANFACTPART") "WR04X1002FTL")
      )
      (libsource (lib "GTS_Database") (part "R"))
    )
    (comp (ref "R236")
      (value "10KΩ")
      (footprint "R0402")
      (description "10KΩ 1% 62.5mW")
      (fields
        (field (name "REFVAL") "10KΩ")
        (field (name "PART NUMBER") "RS0011")
        (field (name "MANFACTPART") "WR04X1002FTL")
      )
      (libsource (lib "GTS_Database") (part "R"))
    )
    (comp (ref "R237")
      (value "43KΩ")
      (footprint "R0402")
      (description "43KΩ 1% 62.5mW 100PPM")
      (fields
        (field (name "REFVAL") "43KΩ")
        (field (name "PART NUMBER") "RS0076")
        (field (name "MANFACTPART") "CRCW040243K0FKEDC")
      )
      (libsource (lib "GTS_Database") (part "R"))
    )
    (comp (ref "R238")
      (value "0Ω")
      (footprint "R0402")
      (description "0Ω 62.5mW")
      (fields
        (field (name "REFVAL") "0Ω")
        (field (name "PART NUMBER") "RS0074")
        (field (name "MANFACTPART") "0402WGJ0000TCE")
      )
      (libsource (lib "GTS_Database") (part "R"))
    )
    (comp (ref "R239")
      (value "0Ω")
      (footprint "R0402")
      (description "0Ω 62.5mW")
      (fields
        (field (name "REFVAL") "0Ω")
        (field (name "PART NUMBER") "RS0074")
        (field (name "MANFACTPART") "0402WGJ0000TCE")
      )
      (libsource (lib "GTS_Database") (part "R"))
    )
    (comp (ref "R240")
      (value "0Ω")
      (footprint "R0402")
      (description "0Ω 62.5mW")
      (fields
        (field (name "REFVAL") "0Ω")
        (field (name "PART NUMBER") "RS0074")
        (field (name "MANFACTPART") "0402WGJ0000TCE")
      )
      (libsource (lib "GTS_Database") (part "R"))
    )
    (comp (ref "R241")
      (value "49.9KΩ")
      (footprint "R0402")
      (description "49.9KΩ 1% 62.5mW 100PPM")
      (fields
        (field (name "REFVAL") "49.9KΩ")
        (field (name "PART NUMBER") "RS0077")
        (field (name "MANFACTPART") "0402WGF4992TCE")
      )
      (libsource (lib "GTS_Database") (part "R"))
    )
    (comp (ref "R242")
      (value "0Ω")
      (footprint "R0402")
      (description "0Ω 62.5mW")
      (fields
        (field (name "REFVAL") "0Ω")
        (field (name "PART NUMBER") "RS0074")
        (field (name "MANFACTPART") "0402WGJ0000TCE")
      )
      (libsource (lib "GTS_Database") (part "R"))
    )
    (comp (ref "R243")
      (value "10KΩ")
      (footprint "R0402")
      (description "10KΩ 1% 62.5mW")
      (fields
        (field (name "REFVAL") "10KΩ")
        (field (name "PART NUMBER") "RS0011")
        (field (name "MANFACTPART") "WR04X1002FTL")
      )
      (libsource (lib "GTS_Database") (part "R"))
    )
    (comp (ref "R244")
      (value "33KΩ")
      (footprint "R0402")
      (description "33KΩ 1% 62.5mW 100PPM")
      (fields
        (field (name "REFVAL") "33KΩ")
        (field (name "PART NUMBER") "RS0075")
        (field (name "MANFACTPART") "0402WGF3302TCE")
      )
      (libsource (lib "GTS_Database") (part "R"))
    )
    (comp (ref "R245")
      (value "0Ω")
      (footprint "R0402")
      (description "0Ω 62.5mW")
      (fields
        (field (name "REFVAL") "0Ω")
        (field (name "PART NUMBER") "RS0074")
        (field (name "MANFACTPART") "0402WGJ0000TCE")
      )
      (libsource (lib "GTS_Database") (part "R"))
    )
    (comp (ref "R246")
      (value "0Ω")
      (footprint "R0402")
      (description "0Ω 62.5mW")
      (fields
        (field (name "REFVAL") "0Ω")
        (field (name "PART NUMBER") "RS0074")
        (field (name "MANFACTPART") "0402WGJ0000TCE")
      )
      (libsource (lib "GTS_Database") (part "R"))
    )
    (comp (ref "R247")
      (value "100KΩ")
      (footprint "R0402")
      (description "100KΩ 1% 62.5mW 100PPM")
      (fields
        (field (name "REFVAL") "100KΩ")
        (field (name "PART NUMBER") "RS0036")
        (field (name "MANFACTPART") "AC0402FR-13100KL")
      )
      (libsource (lib "GTS_Database") (part "R"))
    )
    (comp (ref "R248")
      (value "0Ω")
      (footprint "R0402")
      (description "0Ω 62.5mW")
      (fields
        (field (name "REFVAL") "0Ω")
        (field (name "PART NUMBER") "RS0074")
        (field (name "MANFACTPART") "0402WGJ0000TCE")
      )
      (libsource (lib "GTS_Database") (part "R"))
    )
    (comp (ref "R249")
      (value "0Ω")
      (footprint "R0402")
      (description "0Ω 62.5mW")
      (fields
        (field (name "REFVAL") "0Ω")
        (field (name "PART NUMBER") "RS0074")
        (field (name "MANFACTPART") "0402WGJ0000TCE")
      )
      (libsource (lib "GTS_Database") (part "R"))
    )
    (comp (ref "R250")
      (value "0Ω")
      (footprint "R0402")
      (description "0Ω 62.5mW")
      (fields
        (field (name "REFVAL") "0Ω")
        (field (name "PART NUMBER") "RS0074")
        (field (name "MANFACTPART") "0402WGJ0000TCE")
      )
      (libsource (lib "GTS_Database") (part "R"))
    )
    (comp (ref "R251")
      (value "0Ω")
      (footprint "R0402")
      (description "0Ω 62.5mW")
      (fields
        (field (name "REFVAL") "0Ω")
        (field (name "PART NUMBER") "RS0074")
        (field (name "MANFACTPART") "0402WGJ0000TCE")
      )
      (libsource (lib "GTS_Database") (part "R"))
    )
    (comp (ref "SW201")
      (value "TS02")
      (footprint "TS02")
      (description "TACTILE SWITCH SPST")
      (fields
        (field (name "REFVAL") "TS02")
        (field (name "PART NUMBER") "SW0005")
        (field (name "MANFACTPART") "TS02-66-50-BK-160-SCR-D")
      )
      (libsource (lib "GTS_Database") (part "SPST-2-4"))
    )
    (comp (ref "X201")
      (value "25MHz")
      (footprint "403W")
      (description "25MHz 8pF 20PPM")
      (fields
        (field (name "REFVAL") "25MHz")
        (field (name "PART NUMBER") "CR0003")
        (field (name "MANFACTPART") "403WF25012IK")
      )
      (libsource (lib "GTS_Database") (part "Crystal_1_3"))
    )
  )
  (nets
    (net (code "7") (name "+1V1") (class "Default")
      (node (ref "C220") (pin "1") (pinfunction "1_1") (pintype "passive"))
      (node (ref "C221") (pin "1") (pinfunction "1_1") (pintype "passive"))
      (node (ref "C222") (pin "1") (pinfunction "1_1") (pintype "passive"))
      (node (ref "C223") (pin "1") (pinfunction "1_1") (pintype "passive"))
      (node (ref "C224") (pin "1") (pinfunction "1_1") (pintype "passive"))
      (node (ref "C225") (pin "1") (pinfunction "1_1") (pintype "passive"))
      (node (ref "C226") (pin "1") (pinfunction "1_1") (pintype "passive"))
      (node (ref "C227") (pin "1") (pinfunction "1_1") (pintype "passive"))
      (node (ref "C228") (pin "1") (pinfunction "1_1") (pintype "passive"))
      (node (ref "C229") (pin "1") (pinfunction "1_1") (pintype "passive"))
      (node (ref "C230") (pin "1") (pinfunction "1_1") (pintype "passive"))
      (node (ref "C231") (pin "1") (pinfunction "1_1") (pintype "passive"))
      (node (ref "C232") (pin "1") (pinfunction "1_1") (pintype "passive"))
      (node (ref "C233") (pin "1") (pinfunction "1_1") (pintype "passive"))
      (node (ref "C234") (pin "1") (pinfunction "1_1") (pintype "passive"))
      (node (ref "C235") (pin "1") (pinfunction "1_1") (pintype "passive"))
      (node (ref "C236") (pin "1") (pinfunction "1_1") (pintype "passive"))
      (node (ref "C237") (pin "1") (pinfunction "1_1") (pintype "passive"))
      (node (ref "C238") (pin "1") (pinfunction "1_1") (pintype "passive"))
      (node (ref "IC203") (pin "18") (pinfunction "VCORE_18") (pintype "passive"))
      (node (ref "IC203") (pin "25") (pinfunction "VCORE_25") (pintype "passive"))
      (node (ref "IC203") (pin "33") (pinfunction "VCORE_33") (pintype "passive"))
      (node (ref "IC203") (pin "39") (pinfunction "VCORE_39") (pintype "passive"))
      (node (ref "IC203") (pin "55") (pinfunction "VCORE_55") (pintype "passive"))
      (node (ref "IC203") (pin "78") (pinfunction "VCORE_78") (pintype "passive"))
      (node (ref "IC203") (pin "85") (pinfunction "VCORE_85") (pintype "passive"))
      (node (ref "IC203") (pin "9") (pinfunction "VCORE_9") (pintype "passive"))
      (node (ref "IC203") (pin "93") (pinfunction "VCORE_93") (pintype "passive"))
    )
    (net (code "8") (name "+3V3") (class "Default")
      (node (ref "C201") (pin "1") (pinfunction "1_1") (pintype "passive"))
      (node (ref "C202") (pin "1") (pinfunction "1_1") (pintype "passive"))
      (node (ref "C203") (pin "1") (pinfunction "1_1") (pintype "passive"))
      (node (ref "C204") (pin "1") (pinfunction "1_1") (pintype "passive"))
      (node (ref "C205") (pin "1") (pinfunction "1_1") (pintype "passive"))
      (node (ref "C206") (pin "1") (pinfunction "1_1") (pintype "passive"))
      (node (ref "C207") (pin "1") (pinfunction "1_1") (pintype "passive"))
      (node (ref "C208") (pin "1") (pinfunction "1_1") (pintype "passive"))
      (node (ref "C209") (pin "1") (pinfunction "1_1") (pintype "passive"))
      (node (ref "C210") (pin "1") (pinfunction "1_1") (pintype "passive"))
      (node (ref "C211") (pin "1") (pinfunction "1_1") (pintype "passive"))
      (node (ref "C212") (pin "1") (pinfunction "1_1") (pintype "passive"))
      (node (ref "C213") (pin "1") (pinfunction "1_1") (pintype "passive"))
      (node (ref "C214") (pin "1") (pinfunction "1_1") (pintype "passive"))
      (node (ref "C215") (pin "1") (pinfunction "1_1") (pintype "passive"))
      (node (ref "C216") (pin "1") (pinfunction "1_1") (pintype "passive"))
      (node (ref "C217") (pin "1") (pinfunction "1_1") (pintype "passive"))
      (node (ref "C246") (pin "1") (pinfunction "1_1") (pintype "passive"))
      (node (ref "D201") (pin "1") (pinfunction "A_1") (pintype "passive"))
      (node (ref "IC203") (pin "26") (pinfunction "VDD33_26") (pintype "passive"))
      (node (ref "IC203") (pin "42") (pinfunction "VDD33_42") (pintype "passive"))
      (node (ref "IC203") (pin "53") (pinfunction "VDD33_53") (pintype "passive"))
      (node (ref "IC203") (pin "62") (pinfunction "VDD33_62") (pintype "passive"))
      (node (ref "IC203") (pin "67") (pinfunction "VDD33_67") (pintype "passive"))
      (node (ref "IC203") (pin "79") (pinfunction "VDD33_79") (pintype "passive"))
      (node (ref "IC203") (pin "88") (pinfunction "VDD33_88") (pintype "passive"))
      (node (ref "IC203") (pin "99") (pinfunction "VDD33_99") (pintype "passive"))
      (node (ref "IC204") (pin "5") (pinfunction "VCC_5") (pintype "passive"))
      (node (ref "R212") (pin "1") (pinfunction "1_1") (pintype "passive"))
      (node (ref "R213") (pin "1") (pinfunction "1_1") (pintype "passive"))
      (node (ref "R214") (pin "1") (pinfunction "1_1") (pintype "passive"))
      (node (ref "R229") (pin "2") (pinfunction "2_2") (pintype "passive"))
      (node (ref "R230") (pin "1") (pinfunction "1_1") (pintype "passive"))
      (node (ref "SW201") (pin "1") (pinfunction "1_1") (pintype "passive"))
      (node (ref "SW201") (pin "2") (pinfunction "2_2") (pintype "passive"))
    )
    (net (code "9") (name "+5VR") (class "Default")
      (node (ref "C218") (pin "1") (pinfunction "1_1") (pintype "passive"))
      (node (ref "C247") (pin "1") (pinfunction "1_1") (pintype "passive"))
      (node (ref "IC201") (pin "8") (pinfunction "VDD_8") (pintype "passive"))
      (node (ref "IC205") (pin "8") (pinfunction "VDD_8") (pintype "passive"))
      (node (ref "R228") (pin "2") (pinfunction "2_2") (pintype "passive"))
      (node (ref "R243") (pin "2") (pinfunction "2_2") (pintype "passive"))
    )
    (net (code "10") (name "+5VU") (class "Default")
      (node (ref "C219") (pin "1") (pinfunction "1_1") (pintype "passive"))
      (node (ref "C239") (pin "1") (pinfunction "1_1") (pintype "passive"))
      (node (ref "C240") (pin "1") (pinfunction "1_1") (pintype "passive"))
      (node (ref "C241") (pin "1") (pinfunction "1_1") (pintype "passive"))
      (node (ref "C250") (pin "1") (pinfunction "1_1") (pintype "passive"))
      (node (ref "C253") (pin "1") (pinfunction "1_1") (pintype "passive"))
      (node (ref "C254") (pin "1") (pinfunction "1_1") (pintype "passive"))
      (node (ref "C255") (pin "1") (pinfunction "1_1") (pintype "passive"))
      (node (ref "IC201") (pin "10") (pinfunction "VS_10") (pintype "passive"))
      (node (ref "IC201") (pin "6") (pinfunction "VS_6") (pintype "passive"))
      (node (ref "IC201") (pin "7") (pinfunction "VS_7") (pintype "passive"))
      (node (ref "IC201") (pin "9") (pinfunction "VS_9") (pintype "passive"))
      (node (ref "IC205") (pin "10") (pinfunction "VS_10") (pintype "passive"))
      (node (ref "IC205") (pin "6") (pinfunction "VS_6") (pintype "passive"))
      (node (ref "IC205") (pin "7") (pinfunction "VS_7") (pintype "passive"))
      (node (ref "IC205") (pin "9") (pinfunction "VS_9") (pintype "passive"))
    )
    (net (code "11") (name "/+3V3_U7252") (class "Default")
      (node (ref "C242") (pin "1") (pinfunction "1_1") (pintype "passive"))
      (node (ref "D201") (pin "3") (pinfunction "K_3") (pintype "passive"))
      (node (ref "IC202") (pin "8") (pinfunction "VCC_8") (pintype "passive"))
      (node (ref "J202") (pin "8") (pinfunction "+3V3_8") (pintype "passive"))
      (node (ref "R203") (pin "2") (pinfunction "2_2") (pintype "passive"))
      (node (ref "R204") (pin "2") (pinfunction "2_2") (pintype "passive"))
      (node (ref "R234") (pin "2") (pinfunction "2_2") (pintype "passive"))
    )
    (net (code "12") (name "/ACTIVE_USB") (class "Default")
      (node (ref "R217") (pin "2") (pinfunction "2_2") (pintype "passive"))
    )
    (net (code "14") (name "/ALERT_1") (class "Default")
      (node (ref "IC201") (pin "20") (pinfunction "ALERT#1_20") (pintype "passive"))
      (node (ref "R248") (pin "1") (pinfunction "1_1") (pintype "passive"))
    )
    (net (code "15") (name "/ALERT_2") (class "Default")
      (node (ref "IC205") (pin "20") (pinfunction "ALERT#1_20") (pintype "passive"))
      (node (ref "R250") (pin "1") (pinfunction "1_1") (pintype "passive"))
    )
    (net (code "16") (name "/ALERT_3") (class "Default")
      (node (ref "IC201") (pin "16") (pinfunction "ALERT#2_16") (pintype "passive"))
      (node (ref "R249") (pin "1") (pinfunction "1_1") (pintype "passive"))
    )
    (net (code "17") (name "/ALERT_4") (class "Default")
      (node (ref "IC205") (pin "16") (pinfunction "ALERT#2_16") (pintype "passive"))
      (node (ref "R251") (pin "1") (pinfunction "1_1") (pintype "passive"))
    )
    (net (code "18") (name "/CFG_STRAP1") (class "Default")
      (node (ref "IC203") (pin "21") (pinfunction "CFG_STRAP1_21") (pintype "passive"))
      (node (ref "J201") (pin "2") (pinfunction "2_2") (pintype "passive"))
      (node (ref "J201") (pin "5") (pinfunction "5_5") (pintype "passive"))
    )
    (net (code "19") (name "/CFG_STRAP2") (class "Default")
      (node (ref "IC203") (pin "22") (pinfunction "CFG_STRAP2_22") (pintype "passive"))
      (node (ref "R209") (pin "2") (pinfunction "2_2") (pintype "passive"))
    )
    (net (code "20") (name "/CFG_STRAP3") (class "Default")
      (node (ref "IC203") (pin "23") (pinfunction "CFG_STRAP3_23") (pintype "passive"))
      (node (ref "R210") (pin "2") (pinfunction "2_2") (pintype "passive"))
    )
    (net (code "21") (name "/COMM_ILIM_13") (class "Default")
      (node (ref "IC201") (pin "3") (pinfunction "COMM_ILIM_3") (pintype "passive"))
      (node (ref "R227") (pin "2") (pinfunction "2_2") (pintype "passive"))
    )
    (net (code "22") (name "/COMM_ILIM_24") (class "Default")
      (node (ref "IC205") (pin "3") (pinfunction "COMM_ILIM_3") (pintype "passive"))
      (node (ref "R244") (pin "2") (pinfunction "2_2") (pintype "passive"))
    )
    (net (code "24") (name "/DP1_DISCH") (class "Default")
      (node (ref "IC203") (pin "46") (pinfunction "PF5_46") (pintype "passive"))
      (node (ref "R222") (pin "2") (pinfunction "2_2") (pintype "passive"))
    )
    (net (code "25") (name "/DP1_VBUS") (class "Default")
      (node (ref "IC203") (pin "4") (pinfunction "DP1_VBUS_MON_4") (pintype "passive"))
      (node (ref "R201") (pin "2") (pinfunction "2_2") (pintype "passive"))
      (node (ref "R211") (pin "2") (pinfunction "2_2") (pintype "passive"))
    )
    (net (code "26") (name "/DP1_VCONN1") (class "Default")
      (node (ref "IC203") (pin "43") (pinfunction "PF2_43") (pintype "passive"))
      (node (ref "R219") (pin "2") (pinfunction "2_2") (pintype "passive"))
    )
    (net (code "27") (name "/DP1_VCONN2") (class "Default")
      (node (ref "IC203") (pin "44") (pinfunction "PF3_44") (pintype "passive"))
      (node (ref "R220") (pin "2") (pinfunction "2_2") (pintype "passive"))
    )
    (net (code "28") (name "/DP2_DISCH") (class "Default")
      (node (ref "IC203") (pin "45") (pinfunction "PF4_45") (pintype "passive"))
      (node (ref "R221") (pin "2") (pinfunction "2_2") (pintype "passive"))
    )
    (net (code "29") (name "/DP2_VBUS") (class "Default")
      (node (ref "IC203") (pin "36") (pinfunction "DP2_VBUS_MON_36") (pintype "passive"))
      (node (ref "R237") (pin "2") (pinfunction "2_2") (pintype "passive"))
      (node (ref "R241") (pin "2") (pinfunction "2_2") (pintype "passive"))
    )
    (net (code "30") (name "/DP2_VCONN1") (class "Default")
      (node (ref "IC203") (pin "51") (pinfunction "PF10_51") (pintype "passive"))
      (node (ref "R223") (pin "2") (pinfunction "2_2") (pintype "passive"))
    )
    (net (code "31") (name "/DP2_VCONN2") (class "Default")
      (node (ref "IC203") (pin "52") (pinfunction "PF11_52") (pintype "passive"))
      (node (ref "R224") (pin "2") (pinfunction "2_2") (pintype "passive"))
    )
    (net (code "32") (name "/GPIO70") (class "Default")
      (node (ref "IC203") (pin "47") (pinfunction "PF6_47") (pintype "passive"))
    )
    (net (code "33") (name "/GPIO71") (class "Default")
      (node (ref "IC203") (pin "48") (pinfunction "PF7_48") (pintype "passive"))
    )
    (net (code "34") (name "/GPIO78") (class "Default")
      (node (ref "IC203") (pin "57") (pinfunction "PF14_57") (pintype "passive"))
    )
    (net (code "35") (name "/GPIO91") (class "Default")
      (node (ref "IC203") (pin "76") (pinfunction "PF27_76") (pintype "passive"))
    )
    (net (code "36") (name "/GPIO92") (class "Default")
      (node (ref "IC203") (pin "77") (pinfunction "PF28_77") (pintype "passive"))
    )
    (net (code "37") (name "/I2C0_SCL_Zero") (class "Default")
      (node (ref "IC203") (pin "75") (pinfunction "PF26_75") (pintype "passive"))
      (node (ref "R240") (pin "1") (pinfunction "1_1") (pintype "passive"))
      (node (ref "R246") (pin "1") (pinfunction "1_1") (pintype "passive"))
    )
    (net (code "38") (name "/I2C0_SDA_Zero") (class "Default")
      (node (ref "IC203") (pin "66") (pinfunction "PF19_66") (pintype "passive"))
      (node (ref "R238") (pin "1") (pinfunction "1_1") (pintype "passive"))
      (node (ref "R245") (pin "1") (pinfunction "1_1") (pintype "passive"))
    )
    (net (code "39") (name "/MSTR_I2C_CLK") (class "Default")
      (node (ref "IC203") (pin "2") (pinfunction "PF30_2") (pintype "passive"))
      (node (ref "R225") (pin "2") (pinfunction "2_2") (pintype "passive"))
    )
    (net (code "40") (name "/MSTR_I2C_DATA") (class "Default")
      (node (ref "IC203") (pin "3") (pinfunction "PF31_3") (pintype "passive"))
      (node (ref "R226") (pin "2") (pinfunction "2_2") (pintype "passive"))
    )
    (net (code "41") (name "/PRT_CTL1") (class "Default")
      (node (ref "IC203") (pin "60") (pinfunction "PF17_60") (pintype "passive"))
      (node (ref "R232") (pin "2") (pinfunction "2_2") (pintype "passive"))
    )
    (net (code "42") (name "/PRT_CTL2") (class "Default")
      (node (ref "IC203") (pin "58") (pinfunction "PF15_58") (pintype "passive"))
      (node (ref "R239") (pin "2") (pinfunction "2_2") (pintype "passive"))
    )
    (net (code "43") (name "/PRT_CTL3") (class "Default")
      (node (ref "IC203") (pin "56") (pinfunction "PF13_56") (pintype "passive"))
      (node (ref "R233") (pin "2") (pinfunction "2_2") (pintype "passive"))
    )
    (net (code "44") (name "/PRT_CTL3_U3") (class "Default")
      (node (ref "IC203") (pin "54") (pinfunction "PF12_54") (pintype "passive"))
    )
    (net (code "45") (name "/PRT_CTL4") (class "Default")
      (node (ref "IC203") (pin "59") (pinfunction "PF16_59") (pintype "passive"))
      (node (ref "R242") (pin "2") (pinfunction "2_2") (pintype "passive"))
    )
    (net (code "46") (name "/PWR_EN1") (class "Default")
      (node (ref "IC201") (pin "1") (pinfunction "PWR_EN1_1") (pintype "passive"))
      (node (ref "R232") (pin "1") (pinfunction "1_1") (pintype "passive"))
      (node (ref "R248") (pin "2") (pinfunction "2_2") (pintype "passive"))
    )
    (net (code "47") (name "/PWR_EN2") (class "Default")
      (node (ref "IC205") (pin "1") (pinfunction "PWR_EN1_1") (pintype "passive"))
      (node (ref "R239") (pin "1") (pinfunction "1_1") (pintype "passive"))
      (node (ref "R250") (pin "2") (pinfunction "2_2") (pintype "passive"))
    )
    (net (code "48") (name "/PWR_EN3") (class "Default")
      (node (ref "IC201") (pin "15") (pinfunction "PWR_EN2_15") (pintype "passive"))
      (node (ref "R233") (pin "1") (pinfunction "1_1") (pintype "passive"))
      (node (ref "R249") (pin "2") (pinfunction "2_2") (pintype "passive"))
    )
    (net (code "49") (name "/PWR_EN4") (class "Default")
      (node (ref "IC205") (pin "15") (pinfunction "PWR_EN2_15") (pintype "passive"))
      (node (ref "R242") (pin "1") (pinfunction "1_1") (pintype "passive"))
      (node (ref "R251") (pin "2") (pinfunction "2_2") (pintype "passive"))
    )
    (net (code "52") (name "/SPI_CEN_U7252") (class "Default")
      (node (ref "IC202") (pin "1") (pinfunction "CS_1") (pintype "passive"))
      (node (ref "IC203") (pin "69") (pinfunction "SPI_CE_N/CFG_NON_REM/PF20_69") (pintype "passive"))
      (node (ref "J202") (pin "7") (pinfunction "CE_7") (pintype "passive"))
      (node (ref "R234") (pin "1") (pinfunction "1_1") (pintype "passive"))
    )
    (net (code "53") (name "/SPI_CLK_U7252") (class "Default")
      (node (ref "IC202") (pin "6") (pinfunction "SCK_6") (pintype "passive"))
      (node (ref "IC203") (pin "68") (pinfunction "SPI_CLK/PF21_68") (pintype "passive"))
      (node (ref "J202") (pin "4") (pinfunction "CLK_4") (pintype "passive"))
    )
    (net (code "54") (name "/SPI_HLD_U7252") (class "Default")
      (node (ref "IC202") (pin "7") (pinfunction "HOLD_7") (pintype "passive"))
      (node (ref "IC203") (pin "73") (pinfunction "SPI_D3/PF25_73") (pintype "passive"))
      (node (ref "J202") (pin "6") (pinfunction "HLD_6") (pintype "passive"))
      (node (ref "R203") (pin "1") (pinfunction "1_1") (pintype "passive"))
    )
    (net (code "55") (name "/SPI_MISO_U7252") (class "Default")
      (node (ref "IC202") (pin "2") (pinfunction "SO_2") (pintype "passive"))
      (node (ref "IC203") (pin "71") (pinfunction "SPI_D1/PF23_71") (pintype "passive"))
      (node (ref "J202") (pin "5") (pinfunction "MISO_5") (pintype "passive"))
    )
    (net (code "56") (name "/SPI_MOSI_U7252") (class "Default")
      (node (ref "IC202") (pin "5") (pinfunction "SI_5") (pintype "passive"))
      (node (ref "IC203") (pin "70") (pinfunction "SPI_D0/CFG_BC_EN/PF22_70") (pintype "passive"))
      (node (ref "J202") (pin "2") (pinfunction "MOSI_2") (pintype "passive"))
    )
    (net (code "57") (name "/SPI_WP_U7252") (class "Default")
      (node (ref "IC202") (pin "3") (pinfunction "WP_3") (pintype "passive"))
      (node (ref "IC203") (pin "72") (pinfunction "SPI_D2/PF24_72") (pintype "passive"))
      (node (ref "J202") (pin "3") (pinfunction "WP_3") (pintype "passive"))
      (node (ref "R204") (pin "1") (pinfunction "1_1") (pintype "passive"))
    )
    (net (code "58") (name "/USB2D1_N") (class "Default")
      (node (ref "IC203") (pin "90") (pinfunction "USB2UP_DM_90") (pintype "passive"))
    )
    (net (code "59") (name "/USB2D1_P") (class "Default")
      (node (ref "IC203") (pin "89") (pinfunction "USB2UP_DP_89") (pintype "passive"))
    )
    (net (code "60") (name "/USB3RX1_N") (class "Default")
      (node (ref "C244") (pin "2") (pinfunction "2_2") (pintype "passive"))
    )
    (net (code "61") (name "/USB3RX1_P") (class "Default")
      (node (ref "C243") (pin "2") (pinfunction "2_2") (pintype "passive"))
    )
    (net (code "62") (name "/USB3TX1_N") (class "Default")
      (node (ref "IC203") (pin "94") (pinfunction "USB3UP_RXDP_94") (pintype "passive"))
    )
    (net (code "63") (name "/USB3TX1_P") (class "Default")
      (node (ref "IC203") (pin "95") (pinfunction "USB3UP_RXDM_95") (pintype "passive"))
    )
    (net (code "64") (name "/USB3XRX1_N") (class "Default")
      (node (ref "C244") (pin "1") (pinfunction "1_1") (pintype "passive"))
      (node (ref "IC203") (pin "92") (pinfunction "USB3UP_TXDM_92") (pintype "passive"))
    )
    (net (code "65") (name "/USB3XRX1_P") (class "Default")
      (node (ref "C243") (pin "1") (pinfunction "1_1") (pintype "passive"))
      (node (ref "IC203") (pin "91") (pinfunction "USB3UP_TXDP_91") (pintype "passive"))
    )
    (net (code "66") (name "/USBF1_5V") (class "Default")
      (node (ref "IC201") (pin "4") (pinfunction "VBUS1_4") (pintype "passive"))
      (node (ref "IC201") (pin "5") (pinfunction "VBUS1_5") (pintype "passive"))
      (node (ref "R201") (pin "1") (pinfunction "1_1") (pintype "passive"))
    )
    (net (code "67") (name "/USBF1_CC1") (class "Default")
      (node (ref "IC203") (pin "12") (pinfunction "DP1_CC1_12") (pintype "passive"))
    )
    (net (code "68") (name "/USBF1_CC2") (class "Default")
      (node (ref "IC203") (pin "13") (pinfunction "DP1_CC2_13") (pintype "passive"))
    )
    (net (code "69") (name "/USBF1_N") (class "Default")
      (node (ref "IC203") (pin "6") (pinfunction "USB2DN_DM1/PRT_DIS_M1_6") (pintype "passive"))
    )
    (net (code "70") (name "/USBF1_P") (class "Default")
      (node (ref "IC203") (pin "5") (pinfunction "USB2DN_DP1/PRT_DIS_P1_5") (pintype "passive"))
    )
    (net (code "71") (name "/USBF1_RX1_N") (class "Default")
      (node (ref "IC203") (pin "11") (pinfunction "USB3DN_RXDM1A_11") (pintype "passive"))
    )
    (net (code "72") (name "/USBF1_RX1_P") (class "Default")
      (node (ref "IC203") (pin "10") (pinfunction "USB3DN_RXDP1A_10") (pintype "passive"))
    )
    (net (code "73") (name "/USBF1_RX2_N") (class "Default")
      (node (ref "IC203") (pin "19") (pinfunction "USB3DN_RXDP1B_19") (pintype "passive"))
    )
    (net (code "74") (name "/USBF1_RX2_P") (class "Default")
      (node (ref "IC203") (pin "20") (pinfunction "USB3DN_RXDM1B_20") (pintype "passive"))
    )
    (net (code "75") (name "/USBF1_TX1_N") (class "Default")
      (node (ref "C248") (pin "2") (pinfunction "2_2") (pintype "passive"))
    )
    (net (code "76") (name "/USBF1_TX1_P") (class "Default")
      (node (ref "C245") (pin "2") (pinfunction "2_2") (pintype "passive"))
    )
    (net (code "77") (name "/USBF1_TX2_N") (class "Default")
      (node (ref "C249") (pin "2") (pinfunction "2_2") (pintype "passive"))
    )
    (net (code "78") (name "/USBF1_TX2_P") (class "Default")
      (node (ref "C251") (pin "2") (pinfunction "2_2") (pintype "passive"))
    )
    (net (code "79") (name "/USBF1_XTX1_N") (class "Default")
      (node (ref "C248") (pin "1") (pinfunction "1_1") (pintype "passive"))
      (node (ref "IC203") (pin "8") (pinfunction "USB3DN_TXDM1A_8") (pintype "passive"))
    )
    (net (code "80") (name "/USBF1_XTX1_P") (class "Default")
      (node (ref "C245") (pin "1") (pinfunction "1_1") (pintype "passive"))
      (node (ref "IC203") (pin "7") (pinfunction "USB3DN_TXDP1A_7") (pintype "passive"))
    )
    (net (code "81") (name "/USBF1_XTX2_N") (class "Default")
      (node (ref "C249") (pin "1") (pinfunction "1_1") (pintype "passive"))
      (node (ref "IC203") (pin "16") (pinfunction "USB3DN_TXDP1B_16") (pintype "passive"))
    )
    (net (code "82") (name "/USBF1_XTX2_P") (class "Default")
      (node (ref "C251") (pin "1") (pinfunction "1_1") (pintype "passive"))
      (node (ref "IC203") (pin "17") (pinfunction "USB3DN_TXDM1B_17") (pintype "passive"))
    )
    (net (code "83") (name "/USBF2_5V") (class "Default")
      (node (ref "IC205") (pin "4") (pinfunction "VBUS1_4") (pintype "passive"))
      (node (ref "IC205") (pin "5") (pinfunction "VBUS1_5") (pintype "passive"))
      (node (ref "R237") (pin "1") (pinfunction "1_1") (pintype "passive"))
    )
    (net (code "84") (name "/USBF2_CC1") (class "Default")
      (node (ref "IC203") (pin "27") (pinfunction "DP2_CC1_27") (pintype "passive"))
    )
    (net (code "85") (name "/USBF2_CC2") (class "Default")
      (node (ref "IC203") (pin "28") (pinfunction "DP2_CC2_28") (pintype "passive"))
    )
    (net (code "86") (name "/USBF2_N") (class "Default")
      (node (ref "IC203") (pin "30") (pinfunction "USB2DN_DM2/PRT_DIS_M2_30") (pintype "passive"))
    )
    (net (code "87") (name "/USBF2_P") (class "Default")
      (node (ref "IC203") (pin "29") (pinfunction "USB2DN_DP2/PRT_DIS_P2_29") (pintype "passive"))
    )
    (net (code "88") (name "/USBF2_RX1_N") (class "Default")
      (node (ref "IC203") (pin "35") (pinfunction "USB3DN_RXDM2A_35") (pintype "passive"))
    )
    (net (code "89") (name "/USBF2_RX1_P") (class "Default")
      (node (ref "IC203") (pin "34") (pinfunction "USB3DN_RXDP2A_34") (pintype "passive"))
    )
    (net (code "90") (name "/USBF2_RX2_N") (class "Default")
      (node (ref "IC203") (pin "40") (pinfunction "USB3DN_RXDP2B_40") (pintype "passive"))
    )
    (net (code "91") (name "/USBF2_RX2_P") (class "Default")
      (node (ref "IC203") (pin "41") (pinfunction "USB3DN_RXDM2B_41") (pintype "passive"))
    )
    (net (code "92") (name "/USBF2_TX1_N") (class "Default")
      (node (ref "C256") (pin "2") (pinfunction "2_2") (pintype "passive"))
    )
    (net (code "93") (name "/USBF2_TX1_P") (class "Default")
      (node (ref "C252") (pin "2") (pinfunction "2_2") (pintype "passive"))
    )
    (net (code "94") (name "/USBF2_TX2_N") (class "Default")
      (node (ref "C257") (pin "2") (pinfunction "2_2") (pintype "passive"))
    )
    (net (code "95") (name "/USBF2_TX2_P") (class "Default")
      (node (ref "C258") (pin "2") (pinfunction "2_2") (pintype "passive"))
    )
    (net (code "96") (name "/USBF2_XTX1_N") (class "Default")
      (node (ref "C256") (pin "1") (pinfunction "1_1") (pintype "passive"))
      (node (ref "IC203") (pin "32") (pinfunction "USB3DN_TXDM2A_32") (pintype "passive"))
    )
    (net (code "97") (name "/USBF2_XTX1_P") (class "Default")
      (node (ref "C252") (pin "1") (pinfunction "1_1") (pintype "passive"))
      (node (ref "IC203") (pin "31") (pinfunction "USB3DN_TXDP2A_31") (pintype "passive"))
    )
    (net (code "98") (name "/USBF2_XTX2_N") (class "Default")
      (node (ref "C257") (pin "1") (pinfunction "1_1") (pintype "passive"))
      (node (ref "IC203") (pin "37") (pinfunction "USB3DN_TXDP2B_37") (pintype "passive"))
    )
    (net (code "99") (name "/USBF2_XTX2_P") (class "Default")
      (node (ref "C258") (pin "1") (pinfunction "1_1") (pintype "passive"))
      (node (ref "IC203") (pin "38") (pinfunction "USB3DN_TXDM2B_38") (pintype "passive"))
    )
    (net (code "100") (name "/USBF3_5V") (class "Default")
      (node (ref "IC201") (pin "11") (pinfunction "VBUS2_11") (pintype "passive"))
      (node (ref "IC201") (pin "12") (pinfunction "VBUS2_12") (pintype "passive"))
    )
    (net (code "101") (name "/USBF3_N") (class "Default")
      (node (ref "IC203") (pin "82") (pinfunction "USB2DN_DM3/PRT_DIS_M3_82") (pintype "passive"))
    )
    (net (code "102") (name "/USBF3_P") (class "Default")
      (node (ref "IC203") (pin "81") (pinfunction "USB2DN_DP3/PRT_DIS_P3_81") (pintype "passive"))
    )
    (net (code "103") (name "/USBF3_RX_N") (class "Default")
      (node (ref "IC203") (pin "87") (pinfunction "USB3DN_RXDM3_87") (pintype "passive"))
    )
    (net (code "104") (name "/USBF3_RX_P") (class "Default")
      (node (ref "IC203") (pin "86") (pinfunction "USB3DN_RXDP3_86") (pintype "passive"))
    )
    (net (code "105") (name "/USBF3_TX_N") (class "Default")
      (node (ref "C260") (pin "2") (pinfunction "2_2") (pintype "passive"))
    )
    (net (code "106") (name "/USBF3_TX_P") (class "Default")
      (node (ref "C259") (pin "2") (pinfunction "2_2") (pintype "passive"))
    )
    (net (code "107") (name "/USBF3_XTX_N") (class "Default")
      (node (ref "C260") (pin "1") (pinfunction "1_1") (pintype "passive"))
      (node (ref "IC203") (pin "84") (pinfunction "USB3DN_TXDM3_84") (pintype "passive"))
    )
    (net (code "108") (name "/USBF3_XTX_P") (class "Default")
      (node (ref "C259") (pin "1") (pinfunction "1_1") (pintype "passive"))
      (node (ref "IC203") (pin "83") (pinfunction "USB3DN_TXDP3_83") (pintype "passive"))
    )
    (net (code "109") (name "/USBF4_5V") (class "Default")
      (node (ref "IC205") (pin "11") (pinfunction "VBUS2_11") (pintype "passive"))
      (node (ref "IC205") (pin "12") (pinfunction "VBUS2_12") (pintype "passive"))
    )
    (net (code "110") (name "/USBF4_N") (class "Default")
      (node (ref "IC203") (pin "15") (pinfunction "USB2DN_DM4/PRT_DIS_M4_15") (pintype "passive"))
    )
    (net (code "111") (name "/USBF4_P") (class "Default")
      (node (ref "IC203") (pin "14") (pinfunction "USB2DN_DP4/PRT_DIS_P4_14") (pintype "passive"))
    )
    (net (code "112") (name "/USB_RESET") (class "Default")
      (node (ref "R236") (pin "2") (pinfunction "2_2") (pintype "passive"))
    )
    (net (code "113") (name "/VBUS_UP") (class "Default")
      (node (ref "IC203") (pin "80") (pinfunction "VBUS_MON_UP_80") (pintype "passive"))
      (node (ref "R217") (pin "1") (pinfunction "1_1") (pintype "passive"))
      (node (ref "R218") (pin "2") (pinfunction "2_2") (pintype "passive"))
    )
    (net (code "114") (name "/XTI") (class "Default")
      (node (ref "C261") (pin "2") (pinfunction "2_2") (pintype "passive"))
      (node (ref "IC203") (pin "98") (pinfunction "XTALI/CLK_IN_98") (pintype "passive"))
      (node (ref "X201") (pin "1") (pinfunction "1_1") (pintype "passive"))
    )
    (net (code "115") (name "/XTO") (class "Default")
      (node (ref "C262") (pin "1") (pinfunction "1_1") (pintype "passive"))
      (node (ref "IC203") (pin "97") (pinfunction "XTALO_97") (pintype "passive"))
      (node (ref "X201") (pin "3") (pinfunction "3_3") (pintype "passive"))
    )
    (net (code "122") (name "GND") (class "Default")
      (node (ref "C201") (pin "2") (pinfunction "2_2") (pintype "passive"))
      (node (ref "C202") (pin "2") (pinfunction "2_2") (pintype "passive"))
      (node (ref "C203") (pin "2") (pinfunction "2_2") (pintype "passive"))
      (node (ref "C204") (pin "2") (pinfunction "2_2") (pintype "passive"))
      (node (ref "C205") (pin "2") (pinfunction "2_2") (pintype "passive"))
      (node (ref "C206") (pin "2") (pinfunction "2_2") (pintype "passive"))
      (node (ref "C207") (pin "2") (pinfunction "2_2") (pintype "passive"))
      (node (ref "C208") (pin "2") (pinfunction "2_2") (pintype "passive"))
      (node (ref "C209") (pin "2") (pinfunction "2_2") (pintype "passive"))
      (node (ref "C210") (pin "2") (pinfunction "2_2") (pintype "passive"))
      (node (ref "C211") (pin "2") (pinfunction "2_2") (pintype "passive"))
      (node (ref "C212") (pin "2") (pinfunction "2_2") (pintype "passive"))
      (node (ref "C213") (pin "2") (pinfunction "2_2") (pintype "passive"))
      (node (ref "C214") (pin "2") (pinfunction "2_2") (pintype "passive"))
      (node (ref "C215") (pin "2") (pinfunction "2_2") (pintype "passive"))
      (node (ref "C216") (pin "2") (pinfunction "2_2") (pintype "passive"))
      (node (ref "C217") (pin "2") (pinfunction "2_2") (pintype "passive"))
      (node (ref "C218") (pin "2") (pinfunction "2_2") (pintype "passive"))
      (node (ref "C219") (pin "2") (pinfunction "2_2") (pintype "passive"))
      (node (ref "C220") (pin "2") (pinfunction "2_2") (pintype "passive"))
      (node (ref "C221") (pin "2") (pinfunction "2_2") (pintype "passive"))
      (node (ref "C222") (pin "2") (pinfunction "2_2") (pintype "passive"))
      (node (ref "C223") (pin "2") (pinfunction "2_2") (pintype "passive"))
      (node (ref "C224") (pin "2") (pinfunction "2_2") (pintype "passive"))
      (node (ref "C225") (pin "2") (pinfunction "2_2") (pintype "passive"))
      (node (ref "C226") (pin "2") (pinfunction "2_2") (pintype "passive"))
      (node (ref "C227") (pin "2") (pinfunction "2_2") (pintype "passive"))
      (node (ref "C228") (pin "2") (pinfunction "2_2") (pintype "passive"))
      (node (ref "C229") (pin "2") (pinfunction "2_2") (pintype "passive"))
      (node (ref "C230") (pin "2") (pinfunction "2_2") (pintype "passive"))
      (node (ref "C231") (pin "2") (pinfunction "2_2") (pintype "passive"))
      (node (ref "C232") (pin "2") (pinfunction "2_2") (pintype "passive"))
      (node (ref "C233") (pin "2") (pinfunction "2_2") (pintype "passive"))
      (node (ref "C234") (pin "2") (pinfunction "2_2") (pintype "passive"))
      (node (ref "C235") (pin "2") (pinfunction "2_2") (pintype "passive"))
      (node (ref "C236") (pin "2") (pinfunction "2_2") (pintype "passive"))
      (node (ref "C237") (pin "2") (pinfunction "2_2") (pintype "passive"))
      (node (ref "C238") (pin "2") (pinfunction "2_2") (pintype "passive"))
      (node (ref "C239") (pin "2") (pinfunction "2_2") (pintype "passive"))
      (node (ref "C240") (pin "2") (pinfunction "2_2") (pintype "passive"))
      (node (ref "C241") (pin "2") (pinfunction "2_2") (pintype "passive"))
      (node (ref "C242") (pin "2") (pinfunction "2_2") (pintype "passive"))
      (node (ref "C246") (pin "2") (pinfunction "2_2") (pintype "passive"))
      (node (ref "C247") (pin "2") (pinfunction "2_2") (pintype "passive"))
      (node (ref "C250") (pin "2") (pinfunction "2_2") (pintype "passive"))
      (node (ref "C253") (pin "2") (pinfunction "2_2") (pintype "passive"))
      (node (ref "C254") (pin "2") (pinfunction "2_2") (pintype "passive"))
      (node (ref "C255") (pin "2") (pinfunction "2_2") (pintype "passive"))
      (node (ref "C261") (pin "1") (pinfunction "1_1") (pintype "passive"))
      (node (ref "C262") (pin "2") (pinfunction "2_2") (pintype "passive"))
      (node (ref "IC201") (pin "14") (pinfunction "GND_14") (pintype "passive"))
      (node (ref "IC201") (pin "17") (pinfunction "GND_17") (pintype "passive"))
      (node (ref "IC201") (pin "2") (pinfunction "GND_2") (pintype "passive"))
      (node (ref "IC202") (pin "4") (pinfunction "GND_4") (pintype "passive"))
      (node (ref "IC203") (pin "101") (pinfunction "GND_101") (pintype "passive"))
      (node (ref "IC203") (pin "24") (pinfunction "TESTEN_24") (pintype "passive"))
      (node (ref "IC204") (pin "3") (pinfunction "GND_3") (pintype "passive"))
      (node (ref "IC205") (pin "14") (pinfunction "GND_14") (pintype "passive"))
      (node (ref "IC205") (pin "17") (pinfunction "GND_17") (pintype "passive"))
      (node (ref "IC205") (pin "2") (pinfunction "GND_2") (pintype "passive"))
      (node (ref "J202") (pin "1") (pinfunction "GND_1") (pintype "passive"))
      (node (ref "R202") (pin "1") (pinfunction "1_1") (pintype "passive"))
      (node (ref "R205") (pin "1") (pinfunction "1_1") (pintype "passive"))
      (node (ref "R206") (pin "2") (pinfunction "2_2") (pintype "passive"))
      (node (ref "R209") (pin "1") (pinfunction "1_1") (pintype "passive"))
      (node (ref "R210") (pin "1") (pinfunction "1_1") (pintype "passive"))
      (node (ref "R211") (pin "1") (pinfunction "1_1") (pintype "passive"))
      (node (ref "R216") (pin "1") (pinfunction "1_1") (pintype "passive"))
      (node (ref "R218") (pin "1") (pinfunction "1_1") (pintype "passive"))
      (node (ref "R219") (pin "1") (pinfunction "1_1") (pintype "passive"))
      (node (ref "R220") (pin "1") (pinfunction "1_1") (pintype "passive"))
      (node (ref "R221") (pin "1") (pinfunction "1_1") (pintype "passive"))
      (node (ref "R222") (pin "1") (pinfunction "1_1") (pintype "passive"))
      (node (ref "R223") (pin "1") (pinfunction "1_1") (pintype "passive"))
      (node (ref "R224") (pin "1") (pinfunction "1_1") (pintype "passive"))
      (node (ref "R225") (pin "1") (pinfunction "1_1") (pintype "passive"))
      (node (ref "R226") (pin "1") (pinfunction "1_1") (pintype "passive"))
      (node (ref "R227") (pin "1") (pinfunction "1_1") (pintype "passive"))
      (node (ref "R231") (pin "1") (pinfunction "1_1") (pintype "passive"))
      (node (ref "R241") (pin "1") (pinfunction "1_1") (pintype "passive"))
      (node (ref "R244") (pin "1") (pinfunction "1_1") (pintype "passive"))
      (node (ref "R247") (pin "1") (pinfunction "1_1") (pintype "passive"))
      (node (ref "X201") (pin "2") (pinfunction "2_2") (pintype "passive"))
      (node (ref "X201") (pin "4") (pinfunction "4_4") (pintype "passive"))
    )
    (net (code "123") (name "Net-(IC201-BOOST#)") (class "Default")
      (node (ref "IC201") (pin "13") (pinfunction "BOOST#_13") (pintype "passive"))
      (node (ref "R228") (pin "1") (pinfunction "1_1") (pintype "passive"))
    )
    (net (code "124") (name "Net-(IC201-SMCLK)") (class "Default")
      (node (ref "IC201") (pin "19") (pinfunction "SMCLK_19") (pintype "passive"))
      (node (ref "R240") (pin "2") (pinfunction "2_2") (pintype "passive"))
    )
    (net (code "125") (name "Net-(IC201-SMDATA)") (class "Default")
      (node (ref "IC201") (pin "18") (pinfunction "SMDATA_18") (pintype "passive"))
      (node (ref "R238") (pin "2") (pinfunction "2_2") (pintype "passive"))
    )
    (net (code "126") (name "Net-(IC203-RBIAS)") (class "Default")
      (node (ref "IC203") (pin "100") (pinfunction "RBIAS_100") (pintype "passive"))
      (node (ref "R216") (pin "2") (pinfunction "2_2") (pintype "passive"))
    )
    (net (code "127") (name "Net-(IC203-RESET_N)") (class "Default")
      (node (ref "IC203") (pin "1") (pinfunction "RESET_N_1") (pintype "passive"))
      (node (ref "R215") (pin "2") (pinfunction "2_2") (pintype "passive"))
      (node (ref "R247") (pin "2") (pinfunction "2_2") (pintype "passive"))
    )
    (net (code "128") (name "Net-(IC203-TEST1)") (class "Default")
      (node (ref "IC203") (pin "63") (pinfunction "TEST1_63") (pintype "passive"))
      (node (ref "R212") (pin "2") (pinfunction "2_2") (pintype "passive"))
    )
    (net (code "129") (name "Net-(IC203-TEST2)") (class "Default")
      (node (ref "IC203") (pin "64") (pinfunction "TEST2_64") (pintype "passive"))
      (node (ref "R213") (pin "2") (pinfunction "2_2") (pintype "passive"))
    )
    (net (code "130") (name "Net-(IC203-TEST3)") (class "Default")
      (node (ref "IC203") (pin "65") (pinfunction "TEST3_65") (pintype "passive"))
      (node (ref "R214") (pin "2") (pinfunction "2_2") (pintype "passive"))
    )
    (net (code "131") (name "Net-(IC204-A)") (class "Default")
      (node (ref "IC204") (pin "2") (pinfunction "A_2") (pintype "passive"))
      (node (ref "R205") (pin "2") (pinfunction "2_2") (pintype "passive"))
      (node (ref "R235") (pin "1") (pinfunction "1_1") (pintype "passive"))
    )
    (net (code "132") (name "Net-(IC204-B)") (class "Default")
      (node (ref "IC204") (pin "1") (pinfunction "B_1") (pintype "passive"))
      (node (ref "R202") (pin "2") (pinfunction "2_2") (pintype "passive"))
      (node (ref "R236") (pin "1") (pinfunction "1_1") (pintype "passive"))
    )
    (net (code "133") (name "Net-(IC204-Y)") (class "Default")
      (node (ref "IC204") (pin "4") (pinfunction "Y_4") (pintype "passive"))
      (node (ref "R215") (pin "1") (pinfunction "1_1") (pintype "passive"))
    )
    (net (code "134") (name "Net-(IC205-BOOST#)") (class "Default")
      (node (ref "IC205") (pin "13") (pinfunction "BOOST#_13") (pintype "passive"))
      (node (ref "R243") (pin "1") (pinfunction "1_1") (pintype "passive"))
    )
    (net (code "135") (name "Net-(IC205-SMCLK)") (class "Default")
      (node (ref "IC205") (pin "19") (pinfunction "SMCLK_19") (pintype "passive"))
      (node (ref "R246") (pin "2") (pinfunction "2_2") (pintype "passive"))
    )
    (net (code "136") (name "Net-(IC205-SMDATA)") (class "Default")
      (node (ref "IC205") (pin "18") (pinfunction "SMDATA_18") (pintype "passive"))
      (node (ref "R245") (pin "2") (pinfunction "2_2") (pintype "passive"))
    )
    (net (code "137") (name "Net-(J201-Pad1)") (class "Default")
      (node (ref "J201") (pin "1") (pinfunction "1_1") (pintype "passive"))
      (node (ref "R229") (pin "1") (pinfunction "1_1") (pintype "passive"))
    )
    (net (code "138") (name "Net-(J201-Pad3)") (class "Default")
      (node (ref "J201") (pin "3") (pinfunction "3_3") (pintype "passive"))
      (node (ref "R231") (pin "2") (pinfunction "2_2") (pintype "passive"))
    )
    (net (code "139") (name "Net-(J201-Pad4)") (class "Default")
      (node (ref "J201") (pin "4") (pinfunction "4_4") (pintype "passive"))
      (node (ref "R230") (pin "2") (pinfunction "2_2") (pintype "passive"))
    )
    (net (code "140") (name "Net-(J201-Pad6)") (class "Default")
      (node (ref "J201") (pin "6") (pinfunction "6_6") (pintype "passive"))
      (node (ref "R206") (pin "1") (pinfunction "1_1") (pintype "passive"))
    )
    (net (code "141") (name "Net-(R235-Pad2)") (class "Default")
      (node (ref "R235") (pin "2") (pinfunction "2_2") (pintype "passive"))
      (node (ref "SW201") (pin "3") (pinfunction "3_3") (pintype "passive"))
      (node (ref "SW201") (pin "4") (pinfunction "4_4") (pintype "passive"))
    )
    (net (code "143") (name "unconnected-(IC203-ATEST-Pad96)") (class "Default")
      (node (ref "IC203") (pin "96") (pinfunction "ATEST_96") (pintype "passive+no_connect"))
    )
    (net (code "144") (name "unconnected-(IC203-PF8-Pad49)") (class "Default")
      (node (ref "IC203") (pin "49") (pinfunction "PF8_49") (pintype "passive"))
    )
    (net (code "145") (name "unconnected-(IC203-PF9-Pad50)") (class "Default")
      (node (ref "IC203") (pin "50") (pinfunction "PF9_50") (pintype "passive"))
    )
    (net (code "146") (name "unconnected-(IC203-PF18-Pad61)") (class "Default")
      (node (ref "IC203") (pin "61") (pinfunction "PF18_61") (pintype "passive"))
    )
    (net (code "147") (name "unconnected-(IC203-PF29-Pad74)") (class "Default")
      (node (ref "IC203") (pin "74") (pinfunction "PF29_74") (pintype "passive"))
    )
  )
)
